# House_LED_board.net
KiCad netlist of a schematic drawn in EAGLE
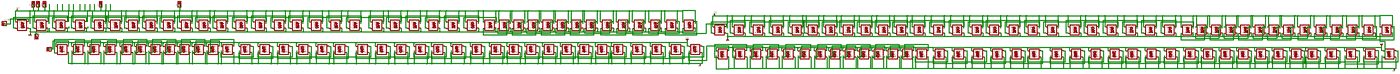
[diagram p0: schematic, sheet 1, overview]
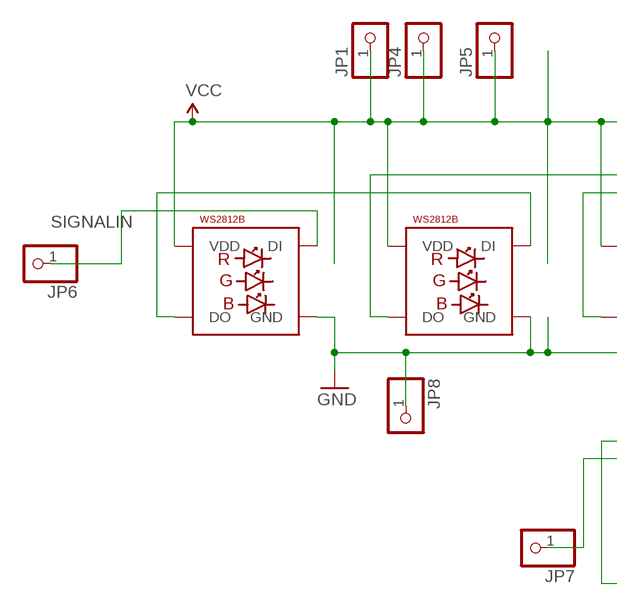
[diagram p1: schematic, sheet 1, part 1 of 8]
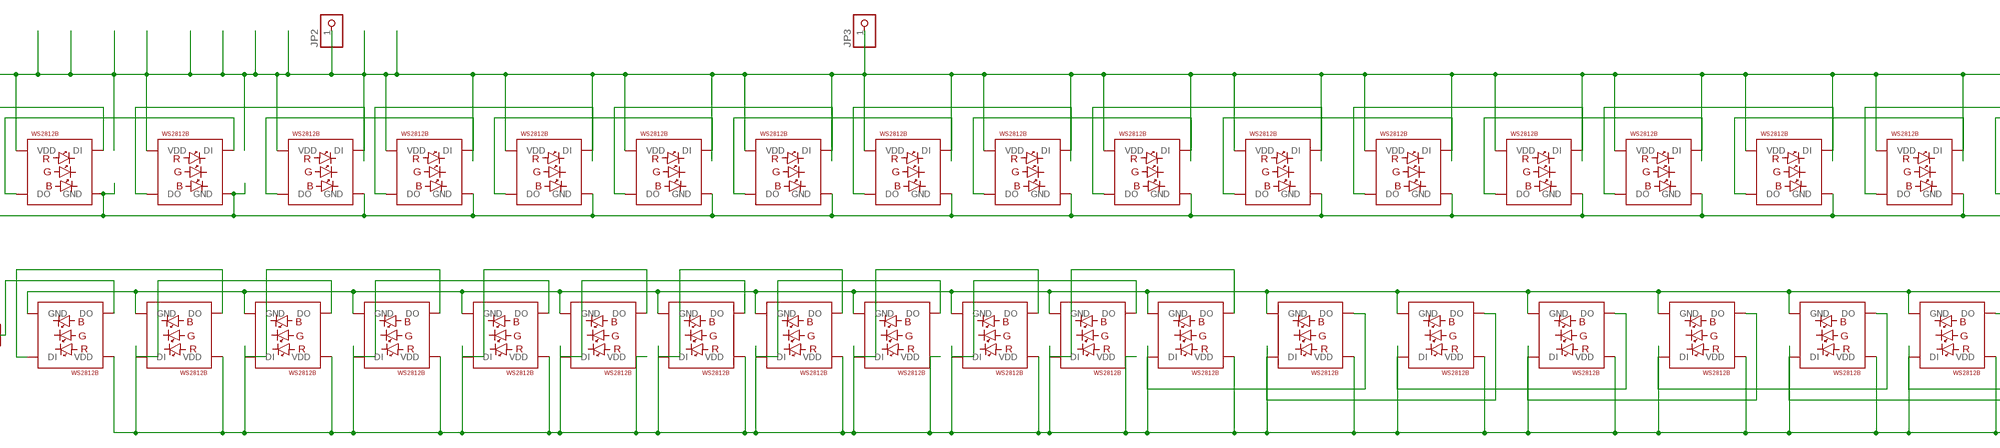
[diagram p2: schematic, sheet 1, part 2 of 8]
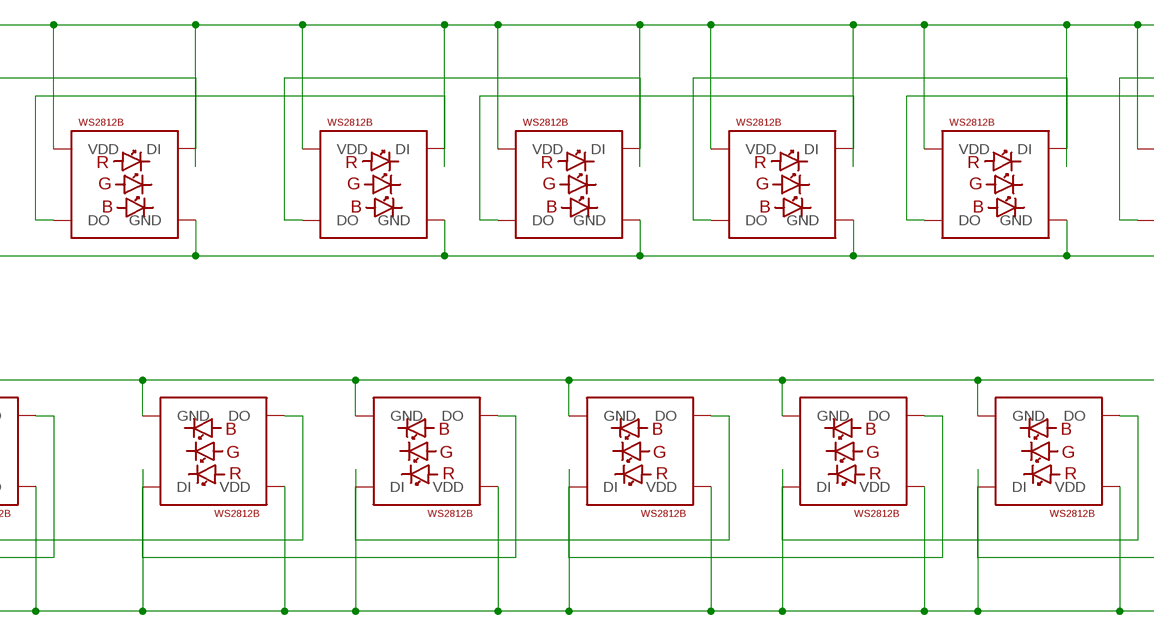
[diagram p3: schematic, sheet 1, part 3 of 8]
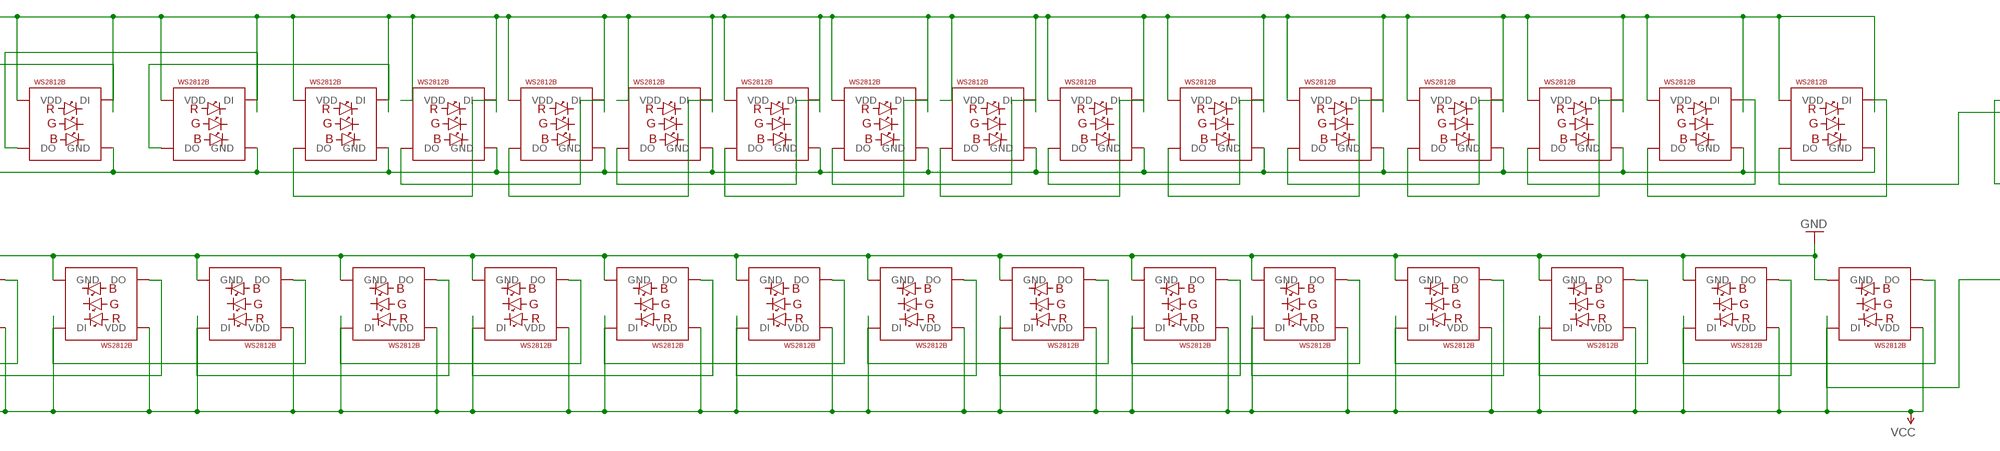
[diagram p4: schematic, sheet 1, part 4 of 8]
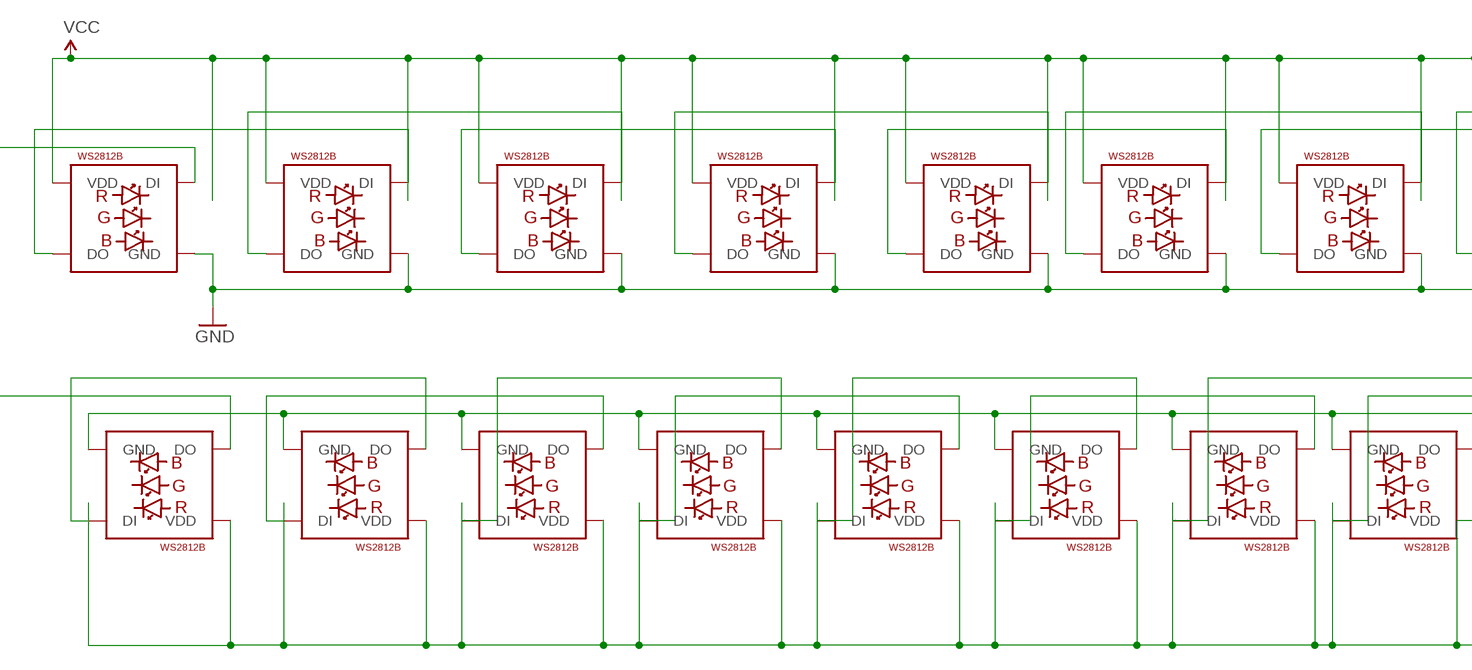
[diagram p5: schematic, sheet 1, part 5 of 8]
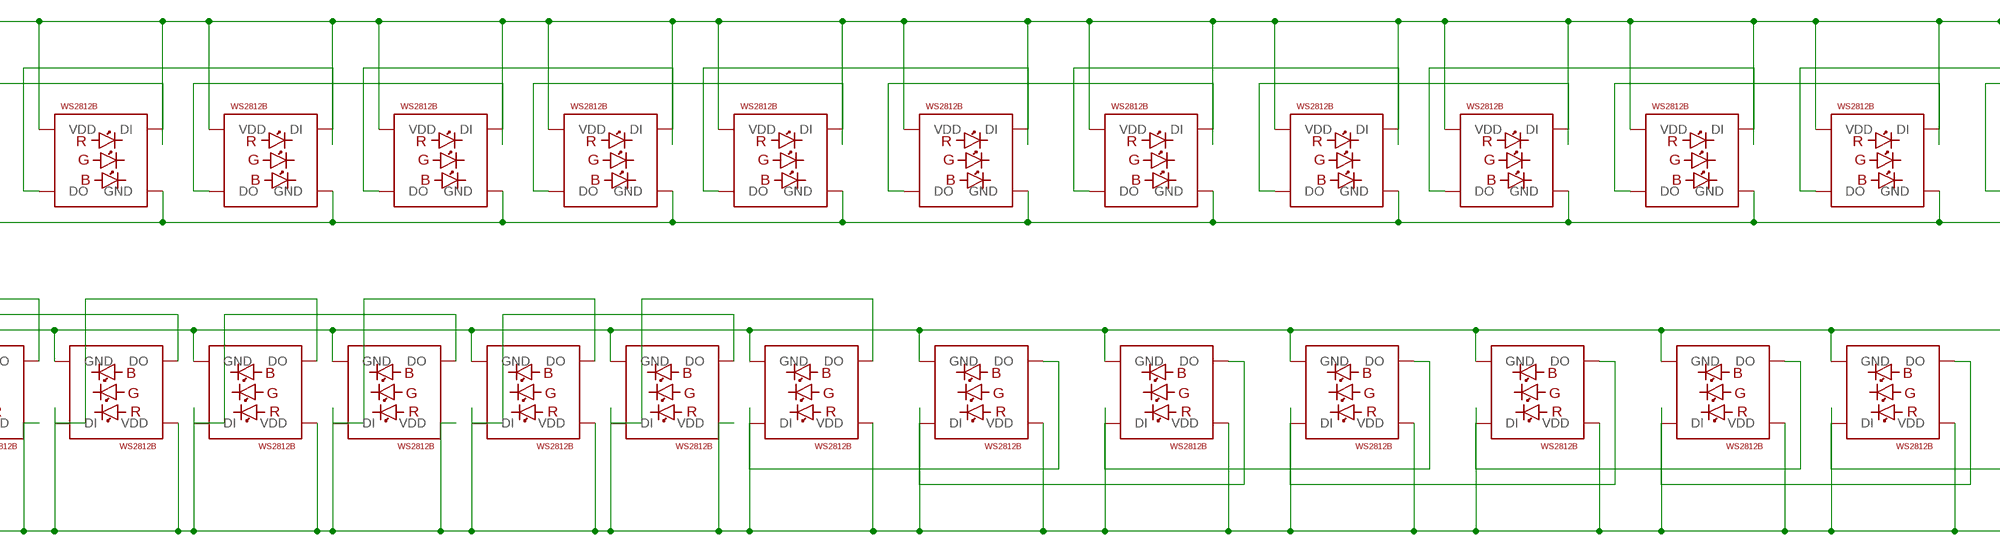
[diagram p6: schematic, sheet 1, part 6 of 8]
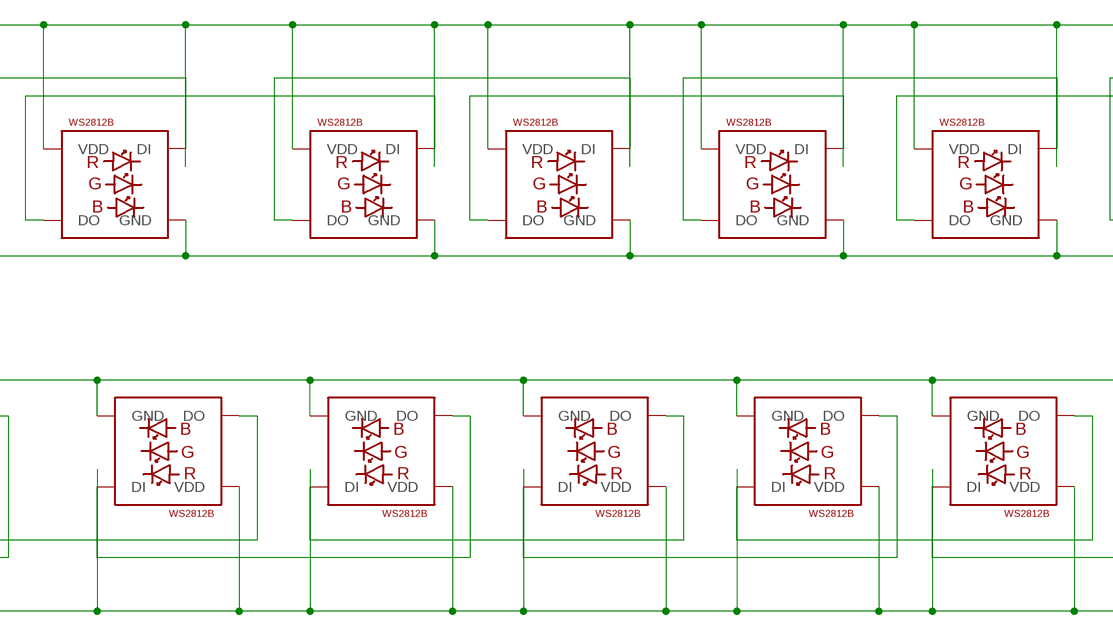
[diagram p7: schematic, sheet 1, part 7 of 8]
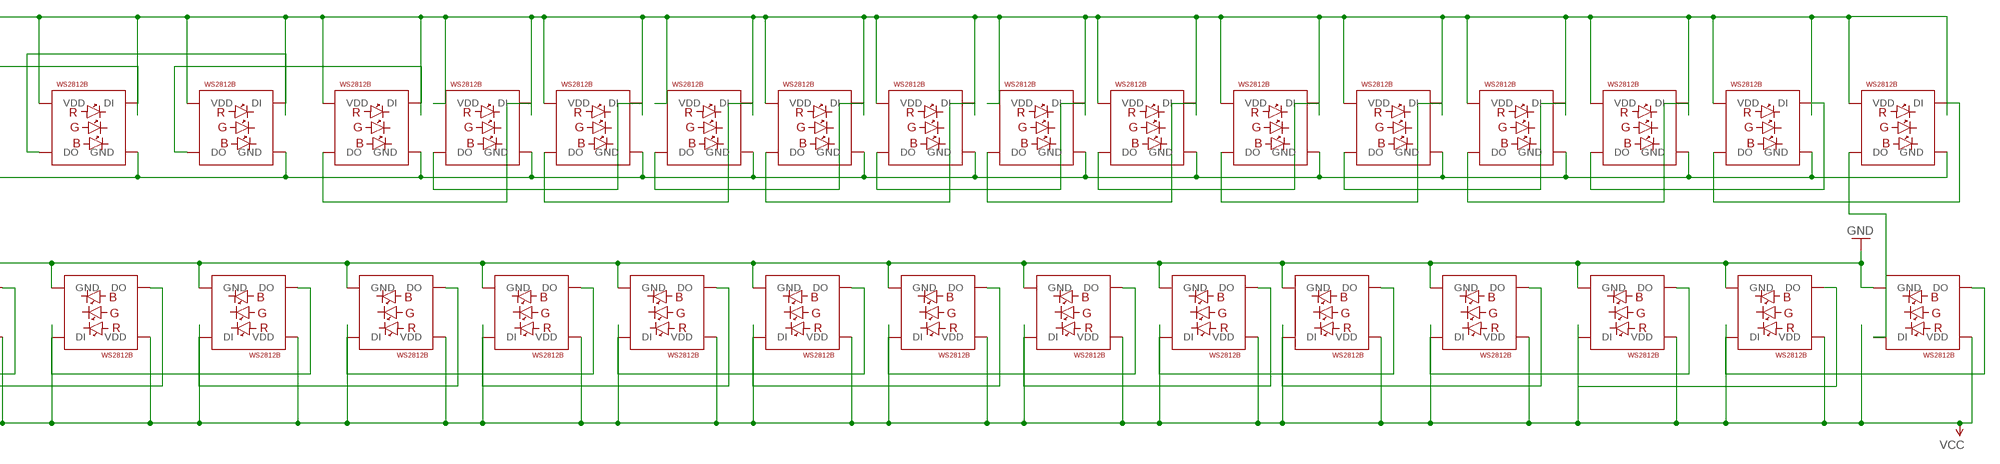
[diagram p8: schematic, sheet 1, part 8 of 8]

(export (version "E")
  (design (tool "Eeschema 10.0.6"))
  (components
    (comp (ref "JP1")
      (value "PINHD-1X1")
      (footprint "eagle-import:1X01")
      (libsource (lib "eagle-import") (part "PINHD-1X1"))
    )
    (comp (ref "JP2")
      (value "PINHD-1X1")
      (footprint "eagle-import:1X01")
      (libsource (lib "eagle-import") (part "PINHD-1X1"))
    )
    (comp (ref "JP3")
      (value "PINHD-1X1")
      (footprint "eagle-import:1X01")
      (libsource (lib "eagle-import") (part "PINHD-1X1"))
    )
    (comp (ref "JP4")
      (value "PINHD-1X1")
      (footprint "eagle-import:1X01")
      (libsource (lib "eagle-import") (part "PINHD-1X1"))
    )
    (comp (ref "JP5")
      (value "PINHD-1X1")
      (footprint "eagle-import:1X01")
      (libsource (lib "eagle-import") (part "PINHD-1X1"))
    )
    (comp (ref "JP6")
      (value "PINHD-1X1")
      (footprint "eagle-import:1X01")
      (libsource (lib "eagle-import") (part "PINHD-1X1"))
    )
    (comp (ref "JP7")
      (value "PINHD-1X1")
      (footprint "eagle-import:1X01")
      (libsource (lib "eagle-import") (part "PINHD-1X1"))
    )
    (comp (ref "JP8")
      (value "PINHD-1X1")
      (footprint "eagle-import:1X01")
      (libsource (lib "eagle-import") (part "PINHD-1X1"))
    )
    (comp (ref "LED1")
      (value "WS2812B5050")
      (footprint "eagle-import:WS2812B")
      (libsource (lib "eagle-import") (part "WS2812B5050"))
    )
    (comp (ref "LED2")
      (value "WS2812B5050")
      (footprint "eagle-import:WS2812B")
      (libsource (lib "eagle-import") (part "WS2812B5050"))
    )
    (comp (ref "LED3")
      (value "WS2812B5050")
      (footprint "eagle-import:WS2812B")
      (libsource (lib "eagle-import") (part "WS2812B5050"))
    )
    (comp (ref "LED4")
      (value "WS2812B5050")
      (footprint "eagle-import:WS2812B")
      (libsource (lib "eagle-import") (part "WS2812B5050"))
    )
    (comp (ref "LED5")
      (value "WS2812B5050")
      (footprint "eagle-import:WS2812B")
      (libsource (lib "eagle-import") (part "WS2812B5050"))
    )
    (comp (ref "LED6")
      (value "WS2812B5050")
      (footprint "eagle-import:WS2812B")
      (libsource (lib "eagle-import") (part "WS2812B5050"))
    )
    (comp (ref "LED7")
      (value "WS2812B5050")
      (footprint "eagle-import:WS2812B")
      (libsource (lib "eagle-import") (part "WS2812B5050"))
    )
    (comp (ref "LED8")
      (value "WS2812B5050")
      (footprint "eagle-import:WS2812B")
      (libsource (lib "eagle-import") (part "WS2812B5050"))
    )
    (comp (ref "LED9")
      (value "WS2812B5050")
      (footprint "eagle-import:WS2812B")
      (libsource (lib "eagle-import") (part "WS2812B5050"))
    )
    (comp (ref "LED10")
      (value "WS2812B5050")
      (footprint "eagle-import:WS2812B")
      (libsource (lib "eagle-import") (part "WS2812B5050"))
    )
    (comp (ref "LED11")
      (value "WS2812B5050")
      (footprint "eagle-import:WS2812B")
      (libsource (lib "eagle-import") (part "WS2812B5050"))
    )
    (comp (ref "LED12")
      (value "WS2812B5050")
      (footprint "eagle-import:WS2812B")
      (libsource (lib "eagle-import") (part "WS2812B5050"))
    )
    (comp (ref "LED13")
      (value "WS2812B5050")
      (footprint "eagle-import:WS2812B")
      (libsource (lib "eagle-import") (part "WS2812B5050"))
    )
    (comp (ref "LED14")
      (value "WS2812B5050")
      (footprint "eagle-import:WS2812B")
      (libsource (lib "eagle-import") (part "WS2812B5050"))
    )
    (comp (ref "LED15")
      (value "WS2812B5050")
      (footprint "eagle-import:WS2812B")
      (libsource (lib "eagle-import") (part "WS2812B5050"))
    )
    (comp (ref "LED16")
      (value "WS2812B5050")
      (footprint "eagle-import:WS2812B")
      (libsource (lib "eagle-import") (part "WS2812B5050"))
    )
    (comp (ref "LED17")
      (value "WS2812B5050")
      (footprint "eagle-import:WS2812B")
      (libsource (lib "eagle-import") (part "WS2812B5050"))
    )
    (comp (ref "LED18")
      (value "WS2812B5050")
      (footprint "eagle-import:WS2812B")
      (libsource (lib "eagle-import") (part "WS2812B5050"))
    )
    (comp (ref "LED19")
      (value "WS2812B5050")
      (footprint "eagle-import:WS2812B")
      (libsource (lib "eagle-import") (part "WS2812B5050"))
    )
    (comp (ref "LED20")
      (value "WS2812B5050")
      (footprint "eagle-import:WS2812B")
      (libsource (lib "eagle-import") (part "WS2812B5050"))
    )
    (comp (ref "LED21")
      (value "WS2812B5050")
      (footprint "eagle-import:WS2812B")
      (libsource (lib "eagle-import") (part "WS2812B5050"))
    )
    (comp (ref "LED22")
      (value "WS2812B5050")
      (footprint "eagle-import:WS2812B")
      (libsource (lib "eagle-import") (part "WS2812B5050"))
    )
    (comp (ref "LED23")
      (value "WS2812B5050")
      (footprint "eagle-import:WS2812B")
      (libsource (lib "eagle-import") (part "WS2812B5050"))
    )
    (comp (ref "LED24")
      (value "WS2812B5050")
      (footprint "eagle-import:WS2812B")
      (libsource (lib "eagle-import") (part "WS2812B5050"))
    )
    (comp (ref "LED25")
      (value "WS2812B5050")
      (footprint "eagle-import:WS2812B")
      (libsource (lib "eagle-import") (part "WS2812B5050"))
    )
    (comp (ref "LED26")
      (value "WS2812B5050")
      (footprint "eagle-import:WS2812B")
      (libsource (lib "eagle-import") (part "WS2812B5050"))
    )
    (comp (ref "LED27")
      (value "WS2812B5050")
      (footprint "eagle-import:WS2812B")
      (libsource (lib "eagle-import") (part "WS2812B5050"))
    )
    (comp (ref "LED28")
      (value "WS2812B5050")
      (footprint "eagle-import:WS2812B")
      (libsource (lib "eagle-import") (part "WS2812B5050"))
    )
    (comp (ref "LED29")
      (value "WS2812B5050")
      (footprint "eagle-import:WS2812B")
      (libsource (lib "eagle-import") (part "WS2812B5050"))
    )
    (comp (ref "LED30")
      (value "WS2812B5050")
      (footprint "eagle-import:WS2812B")
      (libsource (lib "eagle-import") (part "WS2812B5050"))
    )
    (comp (ref "LED31")
      (value "WS2812B5050")
      (footprint "eagle-import:WS2812B")
      (libsource (lib "eagle-import") (part "WS2812B5050"))
    )
    (comp (ref "LED32")
      (value "WS2812B5050")
      (footprint "eagle-import:WS2812B")
      (libsource (lib "eagle-import") (part "WS2812B5050"))
    )
    (comp (ref "LED33")
      (value "WS2812B5050")
      (footprint "eagle-import:WS2812B")
      (libsource (lib "eagle-import") (part "WS2812B5050"))
    )
    (comp (ref "LED34")
      (value "WS2812B5050")
      (footprint "eagle-import:WS2812B")
      (libsource (lib "eagle-import") (part "WS2812B5050"))
    )
    (comp (ref "LED35")
      (value "WS2812B5050")
      (footprint "eagle-import:WS2812B")
      (libsource (lib "eagle-import") (part "WS2812B5050"))
    )
    (comp (ref "LED36")
      (value "WS2812B5050")
      (footprint "eagle-import:WS2812B")
      (libsource (lib "eagle-import") (part "WS2812B5050"))
    )
    (comp (ref "LED37")
      (value "WS2812B5050")
      (footprint "eagle-import:WS2812B")
      (libsource (lib "eagle-import") (part "WS2812B5050"))
    )
    (comp (ref "LED38")
      (value "WS2812B5050")
      (footprint "eagle-import:WS2812B")
      (libsource (lib "eagle-import") (part "WS2812B5050"))
    )
    (comp (ref "LED39")
      (value "WS2812B5050")
      (footprint "eagle-import:WS2812B")
      (libsource (lib "eagle-import") (part "WS2812B5050"))
    )
    (comp (ref "LED40")
      (value "WS2812B5050")
      (footprint "eagle-import:WS2812B")
      (libsource (lib "eagle-import") (part "WS2812B5050"))
    )
    (comp (ref "LED41")
      (value "WS2812B5050")
      (footprint "eagle-import:WS2812B")
      (libsource (lib "eagle-import") (part "WS2812B5050"))
    )
    (comp (ref "LED42")
      (value "WS2812B5050")
      (footprint "eagle-import:WS2812B")
      (libsource (lib "eagle-import") (part "WS2812B5050"))
    )
    (comp (ref "LED43")
      (value "WS2812B5050")
      (footprint "eagle-import:WS2812B")
      (libsource (lib "eagle-import") (part "WS2812B5050"))
    )
    (comp (ref "LED44")
      (value "WS2812B5050")
      (footprint "eagle-import:WS2812B")
      (libsource (lib "eagle-import") (part "WS2812B5050"))
    )
    (comp (ref "LED45")
      (value "WS2812B5050")
      (footprint "eagle-import:WS2812B")
      (libsource (lib "eagle-import") (part "WS2812B5050"))
    )
    (comp (ref "LED46")
      (value "WS2812B5050")
      (footprint "eagle-import:WS2812B")
      (libsource (lib "eagle-import") (part "WS2812B5050"))
    )
    (comp (ref "LED47")
      (value "WS2812B5050")
      (footprint "eagle-import:WS2812B")
      (libsource (lib "eagle-import") (part "WS2812B5050"))
    )
    (comp (ref "LED48")
      (value "WS2812B5050")
      (footprint "eagle-import:WS2812B")
      (libsource (lib "eagle-import") (part "WS2812B5050"))
    )
    (comp (ref "LED49")
      (value "WS2812B5050")
      (footprint "eagle-import:WS2812B")
      (libsource (lib "eagle-import") (part "WS2812B5050"))
    )
    (comp (ref "LED50")
      (value "WS2812B5050")
      (footprint "eagle-import:WS2812B")
      (libsource (lib "eagle-import") (part "WS2812B5050"))
    )
    (comp (ref "LED51")
      (value "WS2812B5050")
      (footprint "eagle-import:WS2812B")
      (libsource (lib "eagle-import") (part "WS2812B5050"))
    )
    (comp (ref "LED52")
      (value "WS2812B5050")
      (footprint "eagle-import:WS2812B")
      (libsource (lib "eagle-import") (part "WS2812B5050"))
    )
    (comp (ref "LED53")
      (value "WS2812B5050")
      (footprint "eagle-import:WS2812B")
      (libsource (lib "eagle-import") (part "WS2812B5050"))
    )
    (comp (ref "LED54")
      (value "WS2812B5050")
      (footprint "eagle-import:WS2812B")
      (libsource (lib "eagle-import") (part "WS2812B5050"))
    )
    (comp (ref "LED55")
      (value "WS2812B5050")
      (footprint "eagle-import:WS2812B")
      (libsource (lib "eagle-import") (part "WS2812B5050"))
    )
    (comp (ref "LED56")
      (value "WS2812B5050")
      (footprint "eagle-import:WS2812B")
      (libsource (lib "eagle-import") (part "WS2812B5050"))
    )
    (comp (ref "LED57")
      (value "WS2812B5050")
      (footprint "eagle-import:WS2812B")
      (libsource (lib "eagle-import") (part "WS2812B5050"))
    )
    (comp (ref "LED58")
      (value "WS2812B5050")
      (footprint "eagle-import:WS2812B")
      (libsource (lib "eagle-import") (part "WS2812B5050"))
    )
    (comp (ref "LED59")
      (value "WS2812B5050")
      (footprint "eagle-import:WS2812B")
      (libsource (lib "eagle-import") (part "WS2812B5050"))
    )
    (comp (ref "LED60")
      (value "WS2812B5050")
      (footprint "eagle-import:WS2812B")
      (libsource (lib "eagle-import") (part "WS2812B5050"))
    )
    (comp (ref "LED61")
      (value "WS2812B5050")
      (footprint "eagle-import:WS2812B")
      (libsource (lib "eagle-import") (part "WS2812B5050"))
    )
    (comp (ref "LED62")
      (value "WS2812B5050")
      (footprint "eagle-import:WS2812B")
      (libsource (lib "eagle-import") (part "WS2812B5050"))
    )
    (comp (ref "LED63")
      (value "WS2812B5050")
      (footprint "eagle-import:WS2812B")
      (libsource (lib "eagle-import") (part "WS2812B5050"))
    )
    (comp (ref "LED64")
      (value "WS2812B5050")
      (footprint "eagle-import:WS2812B")
      (libsource (lib "eagle-import") (part "WS2812B5050"))
    )
    (comp (ref "LED65")
      (value "WS2812B5050")
      (footprint "eagle-import:WS2812B")
      (libsource (lib "eagle-import") (part "WS2812B5050"))
    )
    (comp (ref "LED66")
      (value "WS2812B5050")
      (footprint "eagle-import:WS2812B")
      (libsource (lib "eagle-import") (part "WS2812B5050"))
    )
    (comp (ref "LED67")
      (value "WS2812B5050")
      (footprint "eagle-import:WS2812B")
      (libsource (lib "eagle-import") (part "WS2812B5050"))
    )
    (comp (ref "LED68")
      (value "WS2812B5050")
      (footprint "eagle-import:WS2812B")
      (libsource (lib "eagle-import") (part "WS2812B5050"))
    )
    (comp (ref "LED69")
      (value "WS2812B5050")
      (footprint "eagle-import:WS2812B")
      (libsource (lib "eagle-import") (part "WS2812B5050"))
    )
    (comp (ref "LED70")
      (value "WS2812B5050")
      (footprint "eagle-import:WS2812B")
      (libsource (lib "eagle-import") (part "WS2812B5050"))
    )
    (comp (ref "LED71")
      (value "WS2812B5050")
      (footprint "eagle-import:WS2812B")
      (libsource (lib "eagle-import") (part "WS2812B5050"))
    )
    (comp (ref "LED72")
      (value "WS2812B5050")
      (footprint "eagle-import:WS2812B")
      (libsource (lib "eagle-import") (part "WS2812B5050"))
    )
    (comp (ref "LED73")
      (value "WS2812B5050")
      (footprint "eagle-import:WS2812B")
      (libsource (lib "eagle-import") (part "WS2812B5050"))
    )
    (comp (ref "LED74")
      (value "WS2812B5050")
      (footprint "eagle-import:WS2812B")
      (libsource (lib "eagle-import") (part "WS2812B5050"))
    )
    (comp (ref "LED75")
      (value "WS2812B5050")
      (footprint "eagle-import:WS2812B")
      (libsource (lib "eagle-import") (part "WS2812B5050"))
    )
    (comp (ref "LED76")
      (value "WS2812B5050")
      (footprint "eagle-import:WS2812B")
      (libsource (lib "eagle-import") (part "WS2812B5050"))
    )
    (comp (ref "LED77")
      (value "WS2812B5050")
      (footprint "eagle-import:WS2812B")
      (libsource (lib "eagle-import") (part "WS2812B5050"))
    )
    (comp (ref "LED78")
      (value "WS2812B5050")
      (footprint "eagle-import:WS2812B")
      (libsource (lib "eagle-import") (part "WS2812B5050"))
    )
    (comp (ref "LED79")
      (value "WS2812B5050")
      (footprint "eagle-import:WS2812B")
      (libsource (lib "eagle-import") (part "WS2812B5050"))
    )
    (comp (ref "LED80")
      (value "WS2812B5050")
      (footprint "eagle-import:WS2812B")
      (libsource (lib "eagle-import") (part "WS2812B5050"))
    )
    (comp (ref "LED81")
      (value "WS2812B5050")
      (footprint "eagle-import:WS2812B")
      (libsource (lib "eagle-import") (part "WS2812B5050"))
    )
    (comp (ref "LED82")
      (value "WS2812B5050")
      (footprint "eagle-import:WS2812B")
      (libsource (lib "eagle-import") (part "WS2812B5050"))
    )
    (comp (ref "LED83")
      (value "WS2812B5050")
      (footprint "eagle-import:WS2812B")
      (libsource (lib "eagle-import") (part "WS2812B5050"))
    )
    (comp (ref "LED84")
      (value "WS2812B5050")
      (footprint "eagle-import:WS2812B")
      (libsource (lib "eagle-import") (part "WS2812B5050"))
    )
    (comp (ref "LED85")
      (value "WS2812B5050")
      (footprint "eagle-import:WS2812B")
      (libsource (lib "eagle-import") (part "WS2812B5050"))
    )
    (comp (ref "LED86")
      (value "WS2812B5050")
      (footprint "eagle-import:WS2812B")
      (libsource (lib "eagle-import") (part "WS2812B5050"))
    )
    (comp (ref "LED87")
      (value "WS2812B5050")
      (footprint "eagle-import:WS2812B")
      (libsource (lib "eagle-import") (part "WS2812B5050"))
    )
    (comp (ref "LED88")
      (value "WS2812B5050")
      (footprint "eagle-import:WS2812B")
      (libsource (lib "eagle-import") (part "WS2812B5050"))
    )
    (comp (ref "LED89")
      (value "WS2812B5050")
      (footprint "eagle-import:WS2812B")
      (libsource (lib "eagle-import") (part "WS2812B5050"))
    )
    (comp (ref "LED90")
      (value "WS2812B5050")
      (footprint "eagle-import:WS2812B")
      (libsource (lib "eagle-import") (part "WS2812B5050"))
    )
    (comp (ref "LED91")
      (value "WS2812B5050")
      (footprint "eagle-import:WS2812B")
      (libsource (lib "eagle-import") (part "WS2812B5050"))
    )
    (comp (ref "LED92")
      (value "WS2812B5050")
      (footprint "eagle-import:WS2812B")
      (libsource (lib "eagle-import") (part "WS2812B5050"))
    )
    (comp (ref "LED93")
      (value "WS2812B5050")
      (footprint "eagle-import:WS2812B")
      (libsource (lib "eagle-import") (part "WS2812B5050"))
    )
    (comp (ref "LED94")
      (value "WS2812B5050")
      (footprint "eagle-import:WS2812B")
      (libsource (lib "eagle-import") (part "WS2812B5050"))
    )
    (comp (ref "LED95")
      (value "WS2812B5050")
      (footprint "eagle-import:WS2812B")
      (libsource (lib "eagle-import") (part "WS2812B5050"))
    )
    (comp (ref "LED96")
      (value "WS2812B5050")
      (footprint "eagle-import:WS2812B")
      (libsource (lib "eagle-import") (part "WS2812B5050"))
    )
    (comp (ref "LED97")
      (value "WS2812B5050")
      (footprint "eagle-import:WS2812B")
      (libsource (lib "eagle-import") (part "WS2812B5050"))
    )
    (comp (ref "LED98")
      (value "WS2812B5050")
      (footprint "eagle-import:WS2812B")
      (libsource (lib "eagle-import") (part "WS2812B5050"))
    )
    (comp (ref "LED99")
      (value "WS2812B5050")
      (footprint "eagle-import:WS2812B")
      (libsource (lib "eagle-import") (part "WS2812B5050"))
    )
    (comp (ref "LED100")
      (value "WS2812B5050")
      (footprint "eagle-import:WS2812B")
      (libsource (lib "eagle-import") (part "WS2812B5050"))
    )
    (comp (ref "LED101")
      (value "WS2812B5050")
      (footprint "eagle-import:WS2812B")
      (libsource (lib "eagle-import") (part "WS2812B5050"))
    )
    (comp (ref "LED102")
      (value "WS2812B5050")
      (footprint "eagle-import:WS2812B")
      (libsource (lib "eagle-import") (part "WS2812B5050"))
    )
    (comp (ref "LED103")
      (value "WS2812B5050")
      (footprint "eagle-import:WS2812B")
      (libsource (lib "eagle-import") (part "WS2812B5050"))
    )
    (comp (ref "LED104")
      (value "WS2812B5050")
      (footprint "eagle-import:WS2812B")
      (libsource (lib "eagle-import") (part "WS2812B5050"))
    )
    (comp (ref "LED105")
      (value "WS2812B5050")
      (footprint "eagle-import:WS2812B")
      (libsource (lib "eagle-import") (part "WS2812B5050"))
    )
    (comp (ref "LED106")
      (value "WS2812B5050")
      (footprint "eagle-import:WS2812B")
      (libsource (lib "eagle-import") (part "WS2812B5050"))
    )
    (comp (ref "LED107")
      (value "WS2812B5050")
      (footprint "eagle-import:WS2812B")
      (libsource (lib "eagle-import") (part "WS2812B5050"))
    )
    (comp (ref "LED108")
      (value "WS2812B5050")
      (footprint "eagle-import:WS2812B")
      (libsource (lib "eagle-import") (part "WS2812B5050"))
    )
    (comp (ref "LED109")
      (value "WS2812B5050")
      (footprint "eagle-import:WS2812B")
      (libsource (lib "eagle-import") (part "WS2812B5050"))
    )
    (comp (ref "LED110")
      (value "WS2812B5050")
      (footprint "eagle-import:WS2812B")
      (libsource (lib "eagle-import") (part "WS2812B5050"))
    )
    (comp (ref "LED111")
      (value "WS2812B5050")
      (footprint "eagle-import:WS2812B")
      (libsource (lib "eagle-import") (part "WS2812B5050"))
    )
    (comp (ref "LED112")
      (value "WS2812B5050")
      (footprint "eagle-import:WS2812B")
      (libsource (lib "eagle-import") (part "WS2812B5050"))
    )
    (comp (ref "LED113")
      (value "WS2812B5050")
      (footprint "eagle-import:WS2812B")
      (libsource (lib "eagle-import") (part "WS2812B5050"))
    )
    (comp (ref "LED114")
      (value "WS2812B5050")
      (footprint "eagle-import:WS2812B")
      (libsource (lib "eagle-import") (part "WS2812B5050"))
    )
    (comp (ref "LED115")
      (value "WS2812B5050")
      (footprint "eagle-import:WS2812B")
      (libsource (lib "eagle-import") (part "WS2812B5050"))
    )
    (comp (ref "LED116")
      (value "WS2812B5050")
      (footprint "eagle-import:WS2812B")
      (libsource (lib "eagle-import") (part "WS2812B5050"))
    )
    (comp (ref "LED117")
      (value "WS2812B5050")
      (footprint "eagle-import:WS2812B")
      (libsource (lib "eagle-import") (part "WS2812B5050"))
    )
    (comp (ref "LED118")
      (value "WS2812B5050")
      (footprint "eagle-import:WS2812B")
      (libsource (lib "eagle-import") (part "WS2812B5050"))
    )
    (comp (ref "LED119")
      (value "WS2812B5050")
      (footprint "eagle-import:WS2812B")
      (libsource (lib "eagle-import") (part "WS2812B5050"))
    )
    (comp (ref "LED120")
      (value "WS2812B5050")
      (footprint "eagle-import:WS2812B")
      (libsource (lib "eagle-import") (part "WS2812B5050"))
    )
    (comp (ref "LED121")
      (value "WS2812B5050")
      (footprint "eagle-import:WS2812B")
      (libsource (lib "eagle-import") (part "WS2812B5050"))
    )
    (comp (ref "LED122")
      (value "WS2812B5050")
      (footprint "eagle-import:WS2812B")
      (libsource (lib "eagle-import") (part "WS2812B5050"))
    )
    (comp (ref "LED123")
      (value "WS2812B5050")
      (footprint "eagle-import:WS2812B")
      (libsource (lib "eagle-import") (part "WS2812B5050"))
    )
    (comp (ref "LED124")
      (value "WS2812B5050")
      (footprint "eagle-import:WS2812B")
      (libsource (lib "eagle-import") (part "WS2812B5050"))
    )
    (comp (ref "LED125")
      (value "WS2812B5050")
      (footprint "eagle-import:WS2812B")
      (libsource (lib "eagle-import") (part "WS2812B5050"))
    )
    (comp (ref "LED126")
      (value "WS2812B5050")
      (footprint "eagle-import:WS2812B")
      (libsource (lib "eagle-import") (part "WS2812B5050"))
    )
    (comp (ref "LED127")
      (value "WS2812B5050")
      (footprint "eagle-import:WS2812B")
      (libsource (lib "eagle-import") (part "WS2812B5050"))
    )
    (comp (ref "LED128")
      (value "WS2812B5050")
      (footprint "eagle-import:WS2812B")
      (libsource (lib "eagle-import") (part "WS2812B5050"))
    )
    (comp (ref "LED129")
      (value "WS2812B5050")
      (footprint "eagle-import:WS2812B")
      (libsource (lib "eagle-import") (part "WS2812B5050"))
    )
    (comp (ref "LED130")
      (value "WS2812B5050")
      (footprint "eagle-import:WS2812B")
      (libsource (lib "eagle-import") (part "WS2812B5050"))
    )
    (comp (ref "LED131")
      (value "WS2812B5050")
      (footprint "eagle-import:WS2812B")
      (libsource (lib "eagle-import") (part "WS2812B5050"))
    )
    (comp (ref "LED132")
      (value "WS2812B5050")
      (footprint "eagle-import:WS2812B")
      (libsource (lib "eagle-import") (part "WS2812B5050"))
    )
    (comp (ref "LED133")
      (value "WS2812B5050")
      (footprint "eagle-import:WS2812B")
      (libsource (lib "eagle-import") (part "WS2812B5050"))
    )
    (comp (ref "LED134")
      (value "WS2812B5050")
      (footprint "eagle-import:WS2812B")
      (libsource (lib "eagle-import") (part "WS2812B5050"))
    )
    (comp (ref "LED135")
      (value "WS2812B5050")
      (footprint "eagle-import:WS2812B")
      (libsource (lib "eagle-import") (part "WS2812B5050"))
    )
    (comp (ref "LED136")
      (value "WS2812B5050")
      (footprint "eagle-import:WS2812B")
      (libsource (lib "eagle-import") (part "WS2812B5050"))
    )
    (comp (ref "LED137")
      (value "WS2812B5050")
      (footprint "eagle-import:WS2812B")
      (libsource (lib "eagle-import") (part "WS2812B5050"))
    )
    (comp (ref "LED138")
      (value "WS2812B5050")
      (footprint "eagle-import:WS2812B")
      (libsource (lib "eagle-import") (part "WS2812B5050"))
    )
    (comp (ref "LED139")
      (value "WS2812B5050")
      (footprint "eagle-import:WS2812B")
      (libsource (lib "eagle-import") (part "WS2812B5050"))
    )
    (comp (ref "LED140")
      (value "WS2812B5050")
      (footprint "eagle-import:WS2812B")
      (libsource (lib "eagle-import") (part "WS2812B5050"))
    )
    (comp (ref "LED141")
      (value "WS2812B5050")
      (footprint "eagle-import:WS2812B")
      (libsource (lib "eagle-import") (part "WS2812B5050"))
    )
    (comp (ref "LED142")
      (value "WS2812B5050")
      (footprint "eagle-import:WS2812B")
      (libsource (lib "eagle-import") (part "WS2812B5050"))
    )
    (comp (ref "LED143")
      (value "WS2812B5050")
      (footprint "eagle-import:WS2812B")
      (libsource (lib "eagle-import") (part "WS2812B5050"))
    )
    (comp (ref "LED144")
      (value "WS2812B5050")
      (footprint "eagle-import:WS2812B")
      (libsource (lib "eagle-import") (part "WS2812B5050"))
    )
    (comp (ref "LED145")
      (value "WS2812B5050")
      (footprint "eagle-import:WS2812B")
      (libsource (lib "eagle-import") (part "WS2812B5050"))
    )
    (comp (ref "LED146")
      (value "WS2812B5050")
      (footprint "eagle-import:WS2812B")
      (libsource (lib "eagle-import") (part "WS2812B5050"))
    )
    (comp (ref "LED147")
      (value "WS2812B5050")
      (footprint "eagle-import:WS2812B")
      (libsource (lib "eagle-import") (part "WS2812B5050"))
    )
    (comp (ref "LED148")
      (value "WS2812B5050")
      (footprint "eagle-import:WS2812B")
      (libsource (lib "eagle-import") (part "WS2812B5050"))
    )
    (comp (ref "LED149")
      (value "WS2812B5050")
      (footprint "eagle-import:WS2812B")
      (libsource (lib "eagle-import") (part "WS2812B5050"))
    )
    (comp (ref "LED150")
      (value "WS2812B5050")
      (footprint "eagle-import:WS2812B")
      (libsource (lib "eagle-import") (part "WS2812B5050"))
    )
    (comp (ref "LED151")
      (value "WS2812B5050")
      (footprint "eagle-import:WS2812B")
      (libsource (lib "eagle-import") (part "WS2812B5050"))
    )
    (comp (ref "LED152")
      (value "WS2812B5050")
      (footprint "eagle-import:WS2812B")
      (libsource (lib "eagle-import") (part "WS2812B5050"))
    )
    (comp (ref "LED153")
      (value "WS2812B5050")
      (footprint "eagle-import:WS2812B")
      (libsource (lib "eagle-import") (part "WS2812B5050"))
    )
    (comp (ref "LED154")
      (value "WS2812B5050")
      (footprint "eagle-import:WS2812B")
      (libsource (lib "eagle-import") (part "WS2812B5050"))
    )
  )
  (nets
    (net (code "1") (name "/SIGNALIN") (class "Default")
      (node (ref "JP6") (pin "1") (pinfunction "1_1") (pintype "passive"))
      (node (ref "LED1") (pin "4-DIN") (pinfunction "DI_4-DIN") (pintype "input"))
    )
    (net (code "2") (name "GND") (class "Default")
      (node (ref "JP8") (pin "1") (pinfunction "1_1") (pintype "passive"))
      (node (ref "LED1") (pin "3-GND") (pinfunction "GND_3-GND") (pintype "power_in"))
      (node (ref "LED10") (pin "3-GND") (pinfunction "GND_3-GND") (pintype "power_in"))
      (node (ref "LED100") (pin "3-GND") (pinfunction "GND_3-GND") (pintype "power_in"))
      (node (ref "LED101") (pin "3-GND") (pinfunction "GND_3-GND") (pintype "power_in"))
      (node (ref "LED102") (pin "3-GND") (pinfunction "GND_3-GND") (pintype "power_in"))
      (node (ref "LED103") (pin "3-GND") (pinfunction "GND_3-GND") (pintype "power_in"))
      (node (ref "LED104") (pin "3-GND") (pinfunction "GND_3-GND") (pintype "power_in"))
      (node (ref "LED105") (pin "3-GND") (pinfunction "GND_3-GND") (pintype "power_in"))
      (node (ref "LED106") (pin "3-GND") (pinfunction "GND_3-GND") (pintype "power_in"))
      (node (ref "LED107") (pin "3-GND") (pinfunction "GND_3-GND") (pintype "power_in"))
      (node (ref "LED108") (pin "3-GND") (pinfunction "GND_3-GND") (pintype "power_in"))
      (node (ref "LED109") (pin "3-GND") (pinfunction "GND_3-GND") (pintype "power_in"))
      (node (ref "LED11") (pin "3-GND") (pinfunction "GND_3-GND") (pintype "power_in"))
      (node (ref "LED110") (pin "3-GND") (pinfunction "GND_3-GND") (pintype "power_in"))
      (node (ref "LED111") (pin "3-GND") (pinfunction "GND_3-GND") (pintype "power_in"))
      (node (ref "LED112") (pin "3-GND") (pinfunction "GND_3-GND") (pintype "power_in"))
      (node (ref "LED113") (pin "3-GND") (pinfunction "GND_3-GND") (pintype "power_in"))
      (node (ref "LED114") (pin "3-GND") (pinfunction "GND_3-GND") (pintype "power_in"))
      (node (ref "LED115") (pin "3-GND") (pinfunction "GND_3-GND") (pintype "power_in"))
      (node (ref "LED116") (pin "3-GND") (pinfunction "GND_3-GND") (pintype "power_in"))
      (node (ref "LED117") (pin "3-GND") (pinfunction "GND_3-GND") (pintype "power_in"))
      (node (ref "LED118") (pin "3-GND") (pinfunction "GND_3-GND") (pintype "power_in"))
      (node (ref "LED119") (pin "3-GND") (pinfunction "GND_3-GND") (pintype "power_in"))
      (node (ref "LED12") (pin "3-GND") (pinfunction "GND_3-GND") (pintype "power_in"))
      (node (ref "LED120") (pin "3-GND") (pinfunction "GND_3-GND") (pintype "power_in"))
      (node (ref "LED121") (pin "3-GND") (pinfunction "GND_3-GND") (pintype "power_in"))
      (node (ref "LED122") (pin "3-GND") (pinfunction "GND_3-GND") (pintype "power_in"))
      (node (ref "LED123") (pin "3-GND") (pinfunction "GND_3-GND") (pintype "power_in"))
      (node (ref "LED124") (pin "3-GND") (pinfunction "GND_3-GND") (pintype "power_in"))
      (node (ref "LED125") (pin "3-GND") (pinfunction "GND_3-GND") (pintype "power_in"))
      (node (ref "LED126") (pin "3-GND") (pinfunction "GND_3-GND") (pintype "power_in"))
      (node (ref "LED127") (pin "3-GND") (pinfunction "GND_3-GND") (pintype "power_in"))
      (node (ref "LED128") (pin "3-GND") (pinfunction "GND_3-GND") (pintype "power_in"))
      (node (ref "LED129") (pin "3-GND") (pinfunction "GND_3-GND") (pintype "power_in"))
      (node (ref "LED13") (pin "3-GND") (pinfunction "GND_3-GND") (pintype "power_in"))
      (node (ref "LED130") (pin "3-GND") (pinfunction "GND_3-GND") (pintype "power_in"))
      (node (ref "LED131") (pin "3-GND") (pinfunction "GND_3-GND") (pintype "power_in"))
      (node (ref "LED132") (pin "3-GND") (pinfunction "GND_3-GND") (pintype "power_in"))
      (node (ref "LED133") (pin "3-GND") (pinfunction "GND_3-GND") (pintype "power_in"))
      (node (ref "LED134") (pin "3-GND") (pinfunction "GND_3-GND") (pintype "power_in"))
      (node (ref "LED135") (pin "3-GND") (pinfunction "GND_3-GND") (pintype "power_in"))
      (node (ref "LED136") (pin "3-GND") (pinfunction "GND_3-GND") (pintype "power_in"))
      (node (ref "LED137") (pin "3-GND") (pinfunction "GND_3-GND") (pintype "power_in"))
      (node (ref "LED138") (pin "3-GND") (pinfunction "GND_3-GND") (pintype "power_in"))
      (node (ref "LED139") (pin "3-GND") (pinfunction "GND_3-GND") (pintype "power_in"))
      (node (ref "LED14") (pin "3-GND") (pinfunction "GND_3-GND") (pintype "power_in"))
      (node (ref "LED140") (pin "3-GND") (pinfunction "GND_3-GND") (pintype "power_in"))
      (node (ref "LED141") (pin "3-GND") (pinfunction "GND_3-GND") (pintype "power_in"))
      (node (ref "LED142") (pin "3-GND") (pinfunction "GND_3-GND") (pintype "power_in"))
      (node (ref "LED143") (pin "3-GND") (pinfunction "GND_3-GND") (pintype "power_in"))
      (node (ref "LED144") (pin "3-GND") (pinfunction "GND_3-GND") (pintype "power_in"))
      (node (ref "LED145") (pin "3-GND") (pinfunction "GND_3-GND") (pintype "power_in"))
      (node (ref "LED146") (pin "3-GND") (pinfunction "GND_3-GND") (pintype "power_in"))
      (node (ref "LED147") (pin "3-GND") (pinfunction "GND_3-GND") (pintype "power_in"))
      (node (ref "LED148") (pin "3-GND") (pinfunction "GND_3-GND") (pintype "power_in"))
      (node (ref "LED149") (pin "3-GND") (pinfunction "GND_3-GND") (pintype "power_in"))
      (node (ref "LED15") (pin "3-GND") (pinfunction "GND_3-GND") (pintype "power_in"))
      (node (ref "LED150") (pin "3-GND") (pinfunction "GND_3-GND") (pintype "power_in"))
      (node (ref "LED151") (pin "3-GND") (pinfunction "GND_3-GND") (pintype "power_in"))
      (node (ref "LED152") (pin "3-GND") (pinfunction "GND_3-GND") (pintype "power_in"))
      (node (ref "LED153") (pin "3-GND") (pinfunction "GND_3-GND") (pintype "power_in"))
      (node (ref "LED154") (pin "3-GND") (pinfunction "GND_3-GND") (pintype "power_in"))
      (node (ref "LED16") (pin "3-GND") (pinfunction "GND_3-GND") (pintype "power_in"))
      (node (ref "LED17") (pin "3-GND") (pinfunction "GND_3-GND") (pintype "power_in"))
      (node (ref "LED18") (pin "3-GND") (pinfunction "GND_3-GND") (pintype "power_in"))
      (node (ref "LED19") (pin "3-GND") (pinfunction "GND_3-GND") (pintype "power_in"))
      (node (ref "LED2") (pin "3-GND") (pinfunction "GND_3-GND") (pintype "power_in"))
      (node (ref "LED20") (pin "3-GND") (pinfunction "GND_3-GND") (pintype "power_in"))
      (node (ref "LED21") (pin "3-GND") (pinfunction "GND_3-GND") (pintype "power_in"))
      (node (ref "LED22") (pin "3-GND") (pinfunction "GND_3-GND") (pintype "power_in"))
      (node (ref "LED23") (pin "3-GND") (pinfunction "GND_3-GND") (pintype "power_in"))
      (node (ref "LED24") (pin "3-GND") (pinfunction "GND_3-GND") (pintype "power_in"))
      (node (ref "LED25") (pin "3-GND") (pinfunction "GND_3-GND") (pintype "power_in"))
      (node (ref "LED26") (pin "3-GND") (pinfunction "GND_3-GND") (pintype "power_in"))
      (node (ref "LED27") (pin "3-GND") (pinfunction "GND_3-GND") (pintype "power_in"))
      (node (ref "LED28") (pin "3-GND") (pinfunction "GND_3-GND") (pintype "power_in"))
      (node (ref "LED29") (pin "3-GND") (pinfunction "GND_3-GND") (pintype "power_in"))
      (node (ref "LED3") (pin "3-GND") (pinfunction "GND_3-GND") (pintype "power_in"))
      (node (ref "LED30") (pin "3-GND") (pinfunction "GND_3-GND") (pintype "power_in"))
      (node (ref "LED31") (pin "3-GND") (pinfunction "GND_3-GND") (pintype "power_in"))
      (node (ref "LED32") (pin "3-GND") (pinfunction "GND_3-GND") (pintype "power_in"))
      (node (ref "LED33") (pin "3-GND") (pinfunction "GND_3-GND") (pintype "power_in"))
      (node (ref "LED34") (pin "3-GND") (pinfunction "GND_3-GND") (pintype "power_in"))
      (node (ref "LED35") (pin "3-GND") (pinfunction "GND_3-GND") (pintype "power_in"))
      (node (ref "LED36") (pin "3-GND") (pinfunction "GND_3-GND") (pintype "power_in"))
      (node (ref "LED37") (pin "3-GND") (pinfunction "GND_3-GND") (pintype "power_in"))
      (node (ref "LED38") (pin "3-GND") (pinfunction "GND_3-GND") (pintype "power_in"))
      (node (ref "LED39") (pin "3-GND") (pinfunction "GND_3-GND") (pintype "power_in"))
      (node (ref "LED4") (pin "3-GND") (pinfunction "GND_3-GND") (pintype "power_in"))
      (node (ref "LED40") (pin "3-GND") (pinfunction "GND_3-GND") (pintype "power_in"))
      (node (ref "LED41") (pin "3-GND") (pinfunction "GND_3-GND") (pintype "power_in"))
      (node (ref "LED42") (pin "3-GND") (pinfunction "GND_3-GND") (pintype "power_in"))
      (node (ref "LED43") (pin "3-GND") (pinfunction "GND_3-GND") (pintype "power_in"))
      (node (ref "LED44") (pin "3-GND") (pinfunction "GND_3-GND") (pintype "power_in"))
      (node (ref "LED45") (pin "3-GND") (pinfunction "GND_3-GND") (pintype "power_in"))
      (node (ref "LED46") (pin "3-GND") (pinfunction "GND_3-GND") (pintype "power_in"))
      (node (ref "LED47") (pin "3-GND") (pinfunction "GND_3-GND") (pintype "power_in"))
      (node (ref "LED48") (pin "3-GND") (pinfunction "GND_3-GND") (pintype "power_in"))
      (node (ref "LED49") (pin "3-GND") (pinfunction "GND_3-GND") (pintype "power_in"))
      (node (ref "LED5") (pin "3-GND") (pinfunction "GND_3-GND") (pintype "power_in"))
      (node (ref "LED50") (pin "3-GND") (pinfunction "GND_3-GND") (pintype "power_in"))
      (node (ref "LED51") (pin "3-GND") (pinfunction "GND_3-GND") (pintype "power_in"))
      (node (ref "LED52") (pin "3-GND") (pinfunction "GND_3-GND") (pintype "power_in"))
      (node (ref "LED53") (pin "3-GND") (pinfunction "GND_3-GND") (pintype "power_in"))
      (node (ref "LED54") (pin "3-GND") (pinfunction "GND_3-GND") (pintype "power_in"))
      (node (ref "LED55") (pin "3-GND") (pinfunction "GND_3-GND") (pintype "power_in"))
      (node (ref "LED56") (pin "3-GND") (pinfunction "GND_3-GND") (pintype "power_in"))
      (node (ref "LED57") (pin "3-GND") (pinfunction "GND_3-GND") (pintype "power_in"))
      (node (ref "LED58") (pin "3-GND") (pinfunction "GND_3-GND") (pintype "power_in"))
      (node (ref "LED59") (pin "3-GND") (pinfunction "GND_3-GND") (pintype "power_in"))
      (node (ref "LED6") (pin "3-GND") (pinfunction "GND_3-GND") (pintype "power_in"))
      (node (ref "LED60") (pin "3-GND") (pinfunction "GND_3-GND") (pintype "power_in"))
      (node (ref "LED61") (pin "3-GND") (pinfunction "GND_3-GND") (pintype "power_in"))
      (node (ref "LED62") (pin "3-GND") (pinfunction "GND_3-GND") (pintype "power_in"))
      (node (ref "LED63") (pin "3-GND") (pinfunction "GND_3-GND") (pintype "power_in"))
      (node (ref "LED64") (pin "3-GND") (pinfunction "GND_3-GND") (pintype "power_in"))
      (node (ref "LED65") (pin "3-GND") (pinfunction "GND_3-GND") (pintype "power_in"))
      (node (ref "LED66") (pin "3-GND") (pinfunction "GND_3-GND") (pintype "power_in"))
      (node (ref "LED67") (pin "3-GND") (pinfunction "GND_3-GND") (pintype "power_in"))
      (node (ref "LED68") (pin "3-GND") (pinfunction "GND_3-GND") (pintype "power_in"))
      (node (ref "LED69") (pin "3-GND") (pinfunction "GND_3-GND") (pintype "power_in"))
      (node (ref "LED7") (pin "3-GND") (pinfunction "GND_3-GND") (pintype "power_in"))
      (node (ref "LED70") (pin "3-GND") (pinfunction "GND_3-GND") (pintype "power_in"))
      (node (ref "LED71") (pin "3-GND") (pinfunction "GND_3-GND") (pintype "power_in"))
      (node (ref "LED72") (pin "3-GND") (pinfunction "GND_3-GND") (pintype "power_in"))
      (node (ref "LED73") (pin "3-GND") (pinfunction "GND_3-GND") (pintype "power_in"))
      (node (ref "LED74") (pin "3-GND") (pinfunction "GND_3-GND") (pintype "power_in"))
      (node (ref "LED75") (pin "3-GND") (pinfunction "GND_3-GND") (pintype "power_in"))
      (node (ref "LED76") (pin "3-GND") (pinfunction "GND_3-GND") (pintype "power_in"))
      (node (ref "LED77") (pin "3-GND") (pinfunction "GND_3-GND") (pintype "power_in"))
      (node (ref "LED78") (pin "3-GND") (pinfunction "GND_3-GND") (pintype "power_in"))
      (node (ref "LED79") (pin "3-GND") (pinfunction "GND_3-GND") (pintype "power_in"))
      (node (ref "LED8") (pin "3-GND") (pinfunction "GND_3-GND") (pintype "power_in"))
      (node (ref "LED80") (pin "3-GND") (pinfunction "GND_3-GND") (pintype "power_in"))
      (node (ref "LED81") (pin "3-GND") (pinfunction "GND_3-GND") (pintype "power_in"))
      (node (ref "LED82") (pin "3-GND") (pinfunction "GND_3-GND") (pintype "power_in"))
      (node (ref "LED83") (pin "3-GND") (pinfunction "GND_3-GND") (pintype "power_in"))
      (node (ref "LED84") (pin "3-GND") (pinfunction "GND_3-GND") (pintype "power_in"))
      (node (ref "LED85") (pin "3-GND") (pinfunction "GND_3-GND") (pintype "power_in"))
      (node (ref "LED86") (pin "3-GND") (pinfunction "GND_3-GND") (pintype "power_in"))
      (node (ref "LED87") (pin "3-GND") (pinfunction "GND_3-GND") (pintype "power_in"))
      (node (ref "LED88") (pin "3-GND") (pinfunction "GND_3-GND") (pintype "power_in"))
      (node (ref "LED89") (pin "3-GND") (pinfunction "GND_3-GND") (pintype "power_in"))
      (node (ref "LED9") (pin "3-GND") (pinfunction "GND_3-GND") (pintype "power_in"))
      (node (ref "LED90") (pin "3-GND") (pinfunction "GND_3-GND") (pintype "power_in"))
      (node (ref "LED91") (pin "3-GND") (pinfunction "GND_3-GND") (pintype "power_in"))
      (node (ref "LED92") (pin "3-GND") (pinfunction "GND_3-GND") (pintype "power_in"))
      (node (ref "LED93") (pin "3-GND") (pinfunction "GND_3-GND") (pintype "power_in"))
      (node (ref "LED94") (pin "3-GND") (pinfunction "GND_3-GND") (pintype "power_in"))
      (node (ref "LED95") (pin "3-GND") (pinfunction "GND_3-GND") (pintype "power_in"))
      (node (ref "LED96") (pin "3-GND") (pinfunction "GND_3-GND") (pintype "power_in"))
      (node (ref "LED97") (pin "3-GND") (pinfunction "GND_3-GND") (pintype "power_in"))
      (node (ref "LED98") (pin "3-GND") (pinfunction "GND_3-GND") (pintype "power_in"))
      (node (ref "LED99") (pin "3-GND") (pinfunction "GND_3-GND") (pintype "power_in"))
    )
    (net (code "3") (name "Net-(LED1-DO)") (class "Default")
      (node (ref "LED1") (pin "2-DOUT") (pinfunction "DO_2-DOUT") (pintype "output"))
      (node (ref "LED2") (pin "4-DIN") (pinfunction "DI_4-DIN") (pintype "input"))
    )
    (net (code "4") (name "Net-(LED2-DO)") (class "Default")
      (node (ref "LED2") (pin "2-DOUT") (pinfunction "DO_2-DOUT") (pintype "output"))
      (node (ref "LED3") (pin "4-DIN") (pinfunction "DI_4-DIN") (pintype "input"))
    )
    (net (code "5") (name "Net-(LED3-DO)") (class "Default")
      (node (ref "LED3") (pin "2-DOUT") (pinfunction "DO_2-DOUT") (pintype "output"))
      (node (ref "LED4") (pin "4-DIN") (pinfunction "DI_4-DIN") (pintype "input"))
    )
    (net (code "6") (name "Net-(LED4-DO)") (class "Default")
      (node (ref "LED4") (pin "2-DOUT") (pinfunction "DO_2-DOUT") (pintype "output"))
      (node (ref "LED5") (pin "4-DIN") (pinfunction "DI_4-DIN") (pintype "input"))
    )
    (net (code "7") (name "Net-(LED5-DO)") (class "Default")
      (node (ref "LED5") (pin "2-DOUT") (pinfunction "DO_2-DOUT") (pintype "output"))
      (node (ref "LED6") (pin "4-DIN") (pinfunction "DI_4-DIN") (pintype "input"))
    )
    (net (code "8") (name "Net-(LED6-DO)") (class "Default")
      (node (ref "LED6") (pin "2-DOUT") (pinfunction "DO_2-DOUT") (pintype "output"))
      (node (ref "LED7") (pin "4-DIN") (pinfunction "DI_4-DIN") (pintype "input"))
    )
    (net (code "9") (name "Net-(LED7-DO)") (class "Default")
      (node (ref "LED7") (pin "2-DOUT") (pinfunction "DO_2-DOUT") (pintype "output"))
      (node (ref "LED8") (pin "4-DIN") (pinfunction "DI_4-DIN") (pintype "input"))
    )
    (net (code "10") (name "Net-(LED8-DO)") (class "Default")
      (node (ref "LED8") (pin "2-DOUT") (pinfunction "DO_2-DOUT") (pintype "output"))
      (node (ref "LED9") (pin "4-DIN") (pinfunction "DI_4-DIN") (pintype "input"))
    )
    (net (code "11") (name "Net-(LED10-DI)") (class "Default")
      (node (ref "LED10") (pin "4-DIN") (pinfunction "DI_4-DIN") (pintype "input"))
      (node (ref "LED9") (pin "2-DOUT") (pinfunction "DO_2-DOUT") (pintype "output"))
    )
    (net (code "12") (name "Net-(LED10-DO)") (class "Default")
      (node (ref "LED10") (pin "2-DOUT") (pinfunction "DO_2-DOUT") (pintype "output"))
      (node (ref "LED11") (pin "4-DIN") (pinfunction "DI_4-DIN") (pintype "input"))
    )
    (net (code "13") (name "Net-(LED11-DO)") (class "Default")
      (node (ref "LED11") (pin "2-DOUT") (pinfunction "DO_2-DOUT") (pintype "output"))
      (node (ref "LED12") (pin "4-DIN") (pinfunction "DI_4-DIN") (pintype "input"))
    )
    (net (code "14") (name "Net-(LED12-DO)") (class "Default")
      (node (ref "LED12") (pin "2-DOUT") (pinfunction "DO_2-DOUT") (pintype "output"))
      (node (ref "LED13") (pin "4-DIN") (pinfunction "DI_4-DIN") (pintype "input"))
    )
    (net (code "15") (name "Net-(LED13-DO)") (class "Default")
      (node (ref "LED13") (pin "2-DOUT") (pinfunction "DO_2-DOUT") (pintype "output"))
      (node (ref "LED14") (pin "4-DIN") (pinfunction "DI_4-DIN") (pintype "input"))
    )
    (net (code "16") (name "Net-(LED14-DO)") (class "Default")
      (node (ref "LED14") (pin "2-DOUT") (pinfunction "DO_2-DOUT") (pintype "output"))
      (node (ref "LED15") (pin "4-DIN") (pinfunction "DI_4-DIN") (pintype "input"))
    )
    (net (code "17") (name "Net-(LED15-DO)") (class "Default")
      (node (ref "LED15") (pin "2-DOUT") (pinfunction "DO_2-DOUT") (pintype "output"))
      (node (ref "LED16") (pin "4-DIN") (pinfunction "DI_4-DIN") (pintype "input"))
    )
    (net (code "18") (name "Net-(LED16-DO)") (class "Default")
      (node (ref "LED16") (pin "2-DOUT") (pinfunction "DO_2-DOUT") (pintype "output"))
      (node (ref "LED17") (pin "4-DIN") (pinfunction "DI_4-DIN") (pintype "input"))
    )
    (net (code "19") (name "Net-(LED17-DO)") (class "Default")
      (node (ref "LED17") (pin "2-DOUT") (pinfunction "DO_2-DOUT") (pintype "output"))
      (node (ref "LED18") (pin "4-DIN") (pinfunction "DI_4-DIN") (pintype "input"))
    )
    (net (code "20") (name "Net-(LED18-DO)") (class "Default")
      (node (ref "LED18") (pin "2-DOUT") (pinfunction "DO_2-DOUT") (pintype "output"))
      (node (ref "LED19") (pin "4-DIN") (pinfunction "DI_4-DIN") (pintype "input"))
    )
    (net (code "21") (name "Net-(LED19-DO)") (class "Default")
      (node (ref "LED19") (pin "2-DOUT") (pinfunction "DO_2-DOUT") (pintype "output"))
      (node (ref "LED20") (pin "4-DIN") (pinfunction "DI_4-DIN") (pintype "input"))
    )
    (net (code "22") (name "Net-(LED20-DO)") (class "Default")
      (node (ref "LED20") (pin "2-DOUT") (pinfunction "DO_2-DOUT") (pintype "output"))
      (node (ref "LED21") (pin "4-DIN") (pinfunction "DI_4-DIN") (pintype "input"))
    )
    (net (code "23") (name "Net-(LED21-DO)") (class "Default")
      (node (ref "LED21") (pin "2-DOUT") (pinfunction "DO_2-DOUT") (pintype "output"))
      (node (ref "LED22") (pin "4-DIN") (pinfunction "DI_4-DIN") (pintype "input"))
    )
    (net (code "24") (name "Net-(LED22-DO)") (class "Default")
      (node (ref "LED22") (pin "2-DOUT") (pinfunction "DO_2-DOUT") (pintype "output"))
      (node (ref "LED23") (pin "4-DIN") (pinfunction "DI_4-DIN") (pintype "input"))
    )
    (net (code "25") (name "Net-(LED23-DO)") (class "Default")
      (node (ref "LED23") (pin "2-DOUT") (pinfunction "DO_2-DOUT") (pintype "output"))
      (node (ref "LED24") (pin "4-DIN") (pinfunction "DI_4-DIN") (pintype "input"))
    )
    (net (code "26") (name "Net-(LED24-DO)") (class "Default")
      (node (ref "LED24") (pin "2-DOUT") (pinfunction "DO_2-DOUT") (pintype "output"))
      (node (ref "LED25") (pin "4-DIN") (pinfunction "DI_4-DIN") (pintype "input"))
    )
    (net (code "27") (name "Net-(LED25-DO)") (class "Default")
      (node (ref "LED25") (pin "2-DOUT") (pinfunction "DO_2-DOUT") (pintype "output"))
      (node (ref "LED26") (pin "4-DIN") (pinfunction "DI_4-DIN") (pintype "input"))
    )
    (net (code "28") (name "Net-(LED26-DO)") (class "Default")
      (node (ref "LED26") (pin "2-DOUT") (pinfunction "DO_2-DOUT") (pintype "output"))
      (node (ref "LED27") (pin "4-DIN") (pinfunction "DI_4-DIN") (pintype "input"))
    )
    (net (code "29") (name "Net-(LED27-DO)") (class "Default")
      (node (ref "LED27") (pin "2-DOUT") (pinfunction "DO_2-DOUT") (pintype "output"))
      (node (ref "LED28") (pin "4-DIN") (pinfunction "DI_4-DIN") (pintype "input"))
    )
    (net (code "30") (name "Net-(LED28-DO)") (class "Default")
      (node (ref "LED28") (pin "2-DOUT") (pinfunction "DO_2-DOUT") (pintype "output"))
      (node (ref "LED29") (pin "4-DIN") (pinfunction "DI_4-DIN") (pintype "input"))
    )
    (net (code "31") (name "Net-(LED29-DO)") (class "Default")
      (node (ref "LED29") (pin "2-DOUT") (pinfunction "DO_2-DOUT") (pintype "output"))
      (node (ref "LED30") (pin "4-DIN") (pinfunction "DI_4-DIN") (pintype "input"))
    )
    (net (code "32") (name "Net-(LED30-DO)") (class "Default")
      (node (ref "LED30") (pin "2-DOUT") (pinfunction "DO_2-DOUT") (pintype "output"))
      (node (ref "LED31") (pin "4-DIN") (pinfunction "DI_4-DIN") (pintype "input"))
    )
    (net (code "33") (name "Net-(LED31-DO)") (class "Default")
      (node (ref "LED31") (pin "2-DOUT") (pinfunction "DO_2-DOUT") (pintype "output"))
      (node (ref "LED32") (pin "4-DIN") (pinfunction "DI_4-DIN") (pintype "input"))
    )
    (net (code "34") (name "Net-(LED32-DO)") (class "Default")
      (node (ref "LED32") (pin "2-DOUT") (pinfunction "DO_2-DOUT") (pintype "output"))
      (node (ref "LED33") (pin "4-DIN") (pinfunction "DI_4-DIN") (pintype "input"))
    )
    (net (code "35") (name "Net-(LED33-DO)") (class "Default")
      (node (ref "LED33") (pin "2-DOUT") (pinfunction "DO_2-DOUT") (pintype "output"))
      (node (ref "LED34") (pin "4-DIN") (pinfunction "DI_4-DIN") (pintype "input"))
    )
    (net (code "36") (name "Net-(LED34-DO)") (class "Default")
      (node (ref "LED34") (pin "2-DOUT") (pinfunction "DO_2-DOUT") (pintype "output"))
      (node (ref "LED35") (pin "4-DIN") (pinfunction "DI_4-DIN") (pintype "input"))
    )
    (net (code "37") (name "Net-(LED35-DO)") (class "Default")
      (node (ref "LED35") (pin "2-DOUT") (pinfunction "DO_2-DOUT") (pintype "output"))
      (node (ref "LED36") (pin "4-DIN") (pinfunction "DI_4-DIN") (pintype "input"))
    )
    (net (code "38") (name "Net-(LED36-DO)") (class "Default")
      (node (ref "LED36") (pin "2-DOUT") (pinfunction "DO_2-DOUT") (pintype "output"))
      (node (ref "LED37") (pin "4-DIN") (pinfunction "DI_4-DIN") (pintype "input"))
    )
    (net (code "39") (name "Net-(LED37-DO)") (class "Default")
      (node (ref "LED37") (pin "2-DOUT") (pinfunction "DO_2-DOUT") (pintype "output"))
      (node (ref "LED38") (pin "4-DIN") (pinfunction "DI_4-DIN") (pintype "input"))
    )
    (net (code "40") (name "Net-(LED38-DO)") (class "Default")
      (node (ref "LED38") (pin "2-DOUT") (pinfunction "DO_2-DOUT") (pintype "output"))
      (node (ref "LED39") (pin "4-DIN") (pinfunction "DI_4-DIN") (pintype "input"))
    )
    (net (code "41") (name "Net-(LED39-DO)") (class "Default")
      (node (ref "LED39") (pin "2-DOUT") (pinfunction "DO_2-DOUT") (pintype "output"))
      (node (ref "LED40") (pin "4-DIN") (pinfunction "DI_4-DIN") (pintype "input"))
    )
    (net (code "42") (name "Net-(LED40-DO)") (class "Default")
      (node (ref "LED40") (pin "2-DOUT") (pinfunction "DO_2-DOUT") (pintype "output"))
      (node (ref "LED41") (pin "4-DIN") (pinfunction "DI_4-DIN") (pintype "input"))
    )
    (net (code "43") (name "Net-(LED41-DO)") (class "Default")
      (node (ref "LED41") (pin "2-DOUT") (pinfunction "DO_2-DOUT") (pintype "output"))
      (node (ref "LED42") (pin "4-DIN") (pinfunction "DI_4-DIN") (pintype "input"))
    )
    (net (code "44") (name "Net-(LED42-DO)") (class "Default")
      (node (ref "LED42") (pin "2-DOUT") (pinfunction "DO_2-DOUT") (pintype "output"))
      (node (ref "LED43") (pin "4-DIN") (pinfunction "DI_4-DIN") (pintype "input"))
    )
    (net (code "45") (name "Net-(LED43-DO)") (class "Default")
      (node (ref "LED43") (pin "2-DOUT") (pinfunction "DO_2-DOUT") (pintype "output"))
      (node (ref "LED44") (pin "4-DIN") (pinfunction "DI_4-DIN") (pintype "input"))
    )
    (net (code "46") (name "Net-(LED44-DO)") (class "Default")
      (node (ref "LED44") (pin "2-DOUT") (pinfunction "DO_2-DOUT") (pintype "output"))
      (node (ref "LED45") (pin "4-DIN") (pinfunction "DI_4-DIN") (pintype "input"))
    )
    (net (code "47") (name "Net-(LED45-DO)") (class "Default")
      (node (ref "LED45") (pin "2-DOUT") (pinfunction "DO_2-DOUT") (pintype "output"))
      (node (ref "LED46") (pin "4-DIN") (pinfunction "DI_4-DIN") (pintype "input"))
    )
    (net (code "48") (name "Net-(LED46-DO)") (class "Default")
      (node (ref "LED46") (pin "2-DOUT") (pinfunction "DO_2-DOUT") (pintype "output"))
      (node (ref "LED47") (pin "4-DIN") (pinfunction "DI_4-DIN") (pintype "input"))
    )
    (net (code "49") (name "Net-(LED47-DO)") (class "Default")
      (node (ref "LED47") (pin "2-DOUT") (pinfunction "DO_2-DOUT") (pintype "output"))
      (node (ref "LED48") (pin "4-DIN") (pinfunction "DI_4-DIN") (pintype "input"))
    )
    (net (code "50") (name "Net-(LED48-DO)") (class "Default")
      (node (ref "LED48") (pin "2-DOUT") (pinfunction "DO_2-DOUT") (pintype "output"))
      (node (ref "LED49") (pin "4-DIN") (pinfunction "DI_4-DIN") (pintype "input"))
    )
    (net (code "51") (name "Net-(LED49-DO)") (class "Default")
      (node (ref "LED49") (pin "2-DOUT") (pinfunction "DO_2-DOUT") (pintype "output"))
      (node (ref "LED50") (pin "4-DIN") (pinfunction "DI_4-DIN") (pintype "input"))
    )
    (net (code "52") (name "Net-(LED50-DO)") (class "Default")
      (node (ref "LED50") (pin "2-DOUT") (pinfunction "DO_2-DOUT") (pintype "output"))
      (node (ref "LED51") (pin "4-DIN") (pinfunction "DI_4-DIN") (pintype "input"))
    )
    (net (code "53") (name "Net-(LED51-DO)") (class "Default")
      (node (ref "LED51") (pin "2-DOUT") (pinfunction "DO_2-DOUT") (pintype "output"))
      (node (ref "LED52") (pin "4-DIN") (pinfunction "DI_4-DIN") (pintype "input"))
    )
    (net (code "54") (name "Net-(LED52-DO)") (class "Default")
      (node (ref "LED52") (pin "2-DOUT") (pinfunction "DO_2-DOUT") (pintype "output"))
      (node (ref "LED53") (pin "4-DIN") (pinfunction "DI_4-DIN") (pintype "input"))
    )
    (net (code "55") (name "Net-(LED53-DO)") (class "Default")
      (node (ref "LED53") (pin "2-DOUT") (pinfunction "DO_2-DOUT") (pintype "output"))
      (node (ref "LED54") (pin "4-DIN") (pinfunction "DI_4-DIN") (pintype "input"))
    )
    (net (code "56") (name "Net-(LED54-DO)") (class "Default")
      (node (ref "LED54") (pin "2-DOUT") (pinfunction "DO_2-DOUT") (pintype "output"))
      (node (ref "LED55") (pin "4-DIN") (pinfunction "DI_4-DIN") (pintype "input"))
    )
    (net (code "57") (name "Net-(LED55-DO)") (class "Default")
      (node (ref "LED55") (pin "2-DOUT") (pinfunction "DO_2-DOUT") (pintype "output"))
      (node (ref "LED56") (pin "4-DIN") (pinfunction "DI_4-DIN") (pintype "input"))
    )
    (net (code "58") (name "Net-(LED56-DO)") (class "Default")
      (node (ref "LED56") (pin "2-DOUT") (pinfunction "DO_2-DOUT") (pintype "output"))
      (node (ref "LED57") (pin "4-DIN") (pinfunction "DI_4-DIN") (pintype "input"))
    )
    (net (code "59") (name "Net-(LED57-DO)") (class "Default")
      (node (ref "LED57") (pin "2-DOUT") (pinfunction "DO_2-DOUT") (pintype "output"))
      (node (ref "LED58") (pin "4-DIN") (pinfunction "DI_4-DIN") (pintype "input"))
    )
    (net (code "60") (name "Net-(LED58-DO)") (class "Default")
      (node (ref "LED58") (pin "2-DOUT") (pinfunction "DO_2-DOUT") (pintype "output"))
      (node (ref "LED59") (pin "4-DIN") (pinfunction "DI_4-DIN") (pintype "input"))
    )
    (net (code "61") (name "Net-(LED59-DO)") (class "Default")
      (node (ref "LED59") (pin "2-DOUT") (pinfunction "DO_2-DOUT") (pintype "output"))
      (node (ref "LED60") (pin "4-DIN") (pinfunction "DI_4-DIN") (pintype "input"))
    )
    (net (code "62") (name "Net-(LED60-DO)") (class "Default")
      (node (ref "LED60") (pin "2-DOUT") (pinfunction "DO_2-DOUT") (pintype "output"))
      (node (ref "LED61") (pin "4-DIN") (pinfunction "DI_4-DIN") (pintype "input"))
    )
    (net (code "63") (name "Net-(LED61-DO)") (class "Default")
      (node (ref "LED61") (pin "2-DOUT") (pinfunction "DO_2-DOUT") (pintype "output"))
      (node (ref "LED62") (pin "4-DIN") (pinfunction "DI_4-DIN") (pintype "input"))
    )
    (net (code "64") (name "Net-(LED62-DO)") (class "Default")
      (node (ref "LED62") (pin "2-DOUT") (pinfunction "DO_2-DOUT") (pintype "output"))
      (node (ref "LED63") (pin "4-DIN") (pinfunction "DI_4-DIN") (pintype "input"))
    )
    (net (code "65") (name "Net-(LED63-DO)") (class "Default")
      (node (ref "LED63") (pin "2-DOUT") (pinfunction "DO_2-DOUT") (pintype "output"))
      (node (ref "LED64") (pin "4-DIN") (pinfunction "DI_4-DIN") (pintype "input"))
    )
    (net (code "66") (name "Net-(LED64-DO)") (class "Default")
      (node (ref "LED64") (pin "2-DOUT") (pinfunction "DO_2-DOUT") (pintype "output"))
      (node (ref "LED65") (pin "4-DIN") (pinfunction "DI_4-DIN") (pintype "input"))
    )
    (net (code "67") (name "Net-(LED65-DO)") (class "Default")
      (node (ref "LED65") (pin "2-DOUT") (pinfunction "DO_2-DOUT") (pintype "output"))
      (node (ref "LED66") (pin "4-DIN") (pinfunction "DI_4-DIN") (pintype "input"))
    )
    (net (code "68") (name "Net-(LED66-DO)") (class "Default")
      (node (ref "LED66") (pin "2-DOUT") (pinfunction "DO_2-DOUT") (pintype "output"))
      (node (ref "LED67") (pin "4-DIN") (pinfunction "DI_4-DIN") (pintype "input"))
    )
    (net (code "69") (name "Net-(LED67-DO)") (class "Default")
      (node (ref "LED67") (pin "2-DOUT") (pinfunction "DO_2-DOUT") (pintype "output"))
      (node (ref "LED68") (pin "4-DIN") (pinfunction "DI_4-DIN") (pintype "input"))
    )
    (net (code "70") (name "Net-(LED68-DO)") (class "Default")
      (node (ref "LED68") (pin "2-DOUT") (pinfunction "DO_2-DOUT") (pintype "output"))
      (node (ref "LED69") (pin "4-DIN") (pinfunction "DI_4-DIN") (pintype "input"))
    )
    (net (code "71") (name "Net-(LED69-DO)") (class "Default")
      (node (ref "LED69") (pin "2-DOUT") (pinfunction "DO_2-DOUT") (pintype "output"))
      (node (ref "LED70") (pin "4-DIN") (pinfunction "DI_4-DIN") (pintype "input"))
    )
    (net (code "72") (name "Net-(LED70-DO)") (class "Default")
      (node (ref "LED70") (pin "2-DOUT") (pinfunction "DO_2-DOUT") (pintype "output"))
      (node (ref "LED71") (pin "4-DIN") (pinfunction "DI_4-DIN") (pintype "input"))
    )
    (net (code "73") (name "Net-(LED71-DO)") (class "Default")
      (node (ref "LED71") (pin "2-DOUT") (pinfunction "DO_2-DOUT") (pintype "output"))
      (node (ref "LED72") (pin "4-DIN") (pinfunction "DI_4-DIN") (pintype "input"))
    )
    (net (code "74") (name "Net-(LED72-DO)") (class "Default")
      (node (ref "LED72") (pin "2-DOUT") (pinfunction "DO_2-DOUT") (pintype "output"))
      (node (ref "LED73") (pin "4-DIN") (pinfunction "DI_4-DIN") (pintype "input"))
    )
    (net (code "75") (name "Net-(LED73-DO)") (class "Default")
      (node (ref "LED73") (pin "2-DOUT") (pinfunction "DO_2-DOUT") (pintype "output"))
      (node (ref "LED74") (pin "4-DIN") (pinfunction "DI_4-DIN") (pintype "input"))
    )
    (net (code "76") (name "Net-(LED74-DO)") (class "Default")
      (node (ref "LED74") (pin "2-DOUT") (pinfunction "DO_2-DOUT") (pintype "output"))
      (node (ref "LED75") (pin "4-DIN") (pinfunction "DI_4-DIN") (pintype "input"))
    )
    (net (code "77") (name "Net-(LED75-DO)") (class "Default")
      (node (ref "LED75") (pin "2-DOUT") (pinfunction "DO_2-DOUT") (pintype "output"))
      (node (ref "LED76") (pin "4-DIN") (pinfunction "DI_4-DIN") (pintype "input"))
    )
    (net (code "78") (name "Net-(LED76-DO)") (class "Default")
      (node (ref "LED76") (pin "2-DOUT") (pinfunction "DO_2-DOUT") (pintype "output"))
      (node (ref "LED77") (pin "4-DIN") (pinfunction "DI_4-DIN") (pintype "input"))
    )
    (net (code "79") (name "Net-(LED77-DO)") (class "Default")
      (node (ref "LED77") (pin "2-DOUT") (pinfunction "DO_2-DOUT") (pintype "output"))
      (node (ref "LED78") (pin "4-DIN") (pinfunction "DI_4-DIN") (pintype "input"))
    )
    (net (code "80") (name "Net-(LED78-DO)") (class "Default")
      (node (ref "LED78") (pin "2-DOUT") (pinfunction "DO_2-DOUT") (pintype "output"))
      (node (ref "LED79") (pin "4-DIN") (pinfunction "DI_4-DIN") (pintype "input"))
    )
    (net (code "81") (name "Net-(LED79-DO)") (class "Default")
      (node (ref "LED79") (pin "2-DOUT") (pinfunction "DO_2-DOUT") (pintype "output"))
      (node (ref "LED80") (pin "4-DIN") (pinfunction "DI_4-DIN") (pintype "input"))
    )
    (net (code "82") (name "Net-(LED80-DO)") (class "Default")
      (node (ref "LED80") (pin "2-DOUT") (pinfunction "DO_2-DOUT") (pintype "output"))
      (node (ref "LED81") (pin "4-DIN") (pinfunction "DI_4-DIN") (pintype "input"))
    )
    (net (code "83") (name "Net-(LED81-DO)") (class "Default")
      (node (ref "LED81") (pin "2-DOUT") (pinfunction "DO_2-DOUT") (pintype "output"))
      (node (ref "LED82") (pin "4-DIN") (pinfunction "DI_4-DIN") (pintype "input"))
    )
    (net (code "84") (name "Net-(LED82-DO)") (class "Default")
      (node (ref "LED82") (pin "2-DOUT") (pinfunction "DO_2-DOUT") (pintype "output"))
      (node (ref "LED83") (pin "4-DIN") (pinfunction "DI_4-DIN") (pintype "input"))
    )
    (net (code "85") (name "Net-(LED83-DO)") (class "Default")
      (node (ref "LED83") (pin "2-DOUT") (pinfunction "DO_2-DOUT") (pintype "output"))
      (node (ref "LED84") (pin "4-DIN") (pinfunction "DI_4-DIN") (pintype "input"))
    )
    (net (code "86") (name "Net-(LED84-DO)") (class "Default")
      (node (ref "LED84") (pin "2-DOUT") (pinfunction "DO_2-DOUT") (pintype "output"))
      (node (ref "LED85") (pin "4-DIN") (pinfunction "DI_4-DIN") (pintype "input"))
    )
    (net (code "87") (name "Net-(LED85-DO)") (class "Default")
      (node (ref "LED85") (pin "2-DOUT") (pinfunction "DO_2-DOUT") (pintype "output"))
      (node (ref "LED86") (pin "4-DIN") (pinfunction "DI_4-DIN") (pintype "input"))
    )
    (net (code "88") (name "Net-(LED86-DO)") (class "Default")
      (node (ref "LED86") (pin "2-DOUT") (pinfunction "DO_2-DOUT") (pintype "output"))
      (node (ref "LED87") (pin "4-DIN") (pinfunction "DI_4-DIN") (pintype "input"))
    )
    (net (code "89") (name "Net-(LED87-DO)") (class "Default")
      (node (ref "LED87") (pin "2-DOUT") (pinfunction "DO_2-DOUT") (pintype "output"))
      (node (ref "LED88") (pin "4-DIN") (pinfunction "DI_4-DIN") (pintype "input"))
    )
    (net (code "90") (name "Net-(LED88-DO)") (class "Default")
      (node (ref "LED88") (pin "2-DOUT") (pinfunction "DO_2-DOUT") (pintype "output"))
      (node (ref "LED89") (pin "4-DIN") (pinfunction "DI_4-DIN") (pintype "input"))
    )
    (net (code "91") (name "Net-(LED89-DO)") (class "Default")
      (node (ref "LED89") (pin "2-DOUT") (pinfunction "DO_2-DOUT") (pintype "output"))
      (node (ref "LED90") (pin "4-DIN") (pinfunction "DI_4-DIN") (pintype "input"))
    )
    (net (code "92") (name "Net-(LED90-DO)") (class "Default")
      (node (ref "LED90") (pin "2-DOUT") (pinfunction "DO_2-DOUT") (pintype "output"))
      (node (ref "LED91") (pin "4-DIN") (pinfunction "DI_4-DIN") (pintype "input"))
    )
    (net (code "93") (name "Net-(LED91-DO)") (class "Default")
      (node (ref "LED91") (pin "2-DOUT") (pinfunction "DO_2-DOUT") (pintype "output"))
      (node (ref "LED92") (pin "4-DIN") (pinfunction "DI_4-DIN") (pintype "input"))
    )
    (net (code "94") (name "Net-(LED92-DO)") (class "Default")
      (node (ref "LED92") (pin "2-DOUT") (pinfunction "DO_2-DOUT") (pintype "output"))
      (node (ref "LED93") (pin "4-DIN") (pinfunction "DI_4-DIN") (pintype "input"))
    )
    (net (code "95") (name "Net-(LED93-DO)") (class "Default")
      (node (ref "LED93") (pin "2-DOUT") (pinfunction "DO_2-DOUT") (pintype "output"))
      (node (ref "LED94") (pin "4-DIN") (pinfunction "DI_4-DIN") (pintype "input"))
    )
    (net (code "96") (name "Net-(LED94-DO)") (class "Default")
      (node (ref "LED94") (pin "2-DOUT") (pinfunction "DO_2-DOUT") (pintype "output"))
      (node (ref "LED95") (pin "4-DIN") (pinfunction "DI_4-DIN") (pintype "input"))
    )
    (net (code "97") (name "Net-(LED95-DO)") (class "Default")
      (node (ref "LED95") (pin "2-DOUT") (pinfunction "DO_2-DOUT") (pintype "output"))
      (node (ref "LED96") (pin "4-DIN") (pinfunction "DI_4-DIN") (pintype "input"))
    )
    (net (code "98") (name "Net-(LED96-DO)") (class "Default")
      (node (ref "LED96") (pin "2-DOUT") (pinfunction "DO_2-DOUT") (pintype "output"))
      (node (ref "LED97") (pin "4-DIN") (pinfunction "DI_4-DIN") (pintype "input"))
    )
    (net (code "99") (name "Net-(LED97-DO)") (class "Default")
      (node (ref "LED97") (pin "2-DOUT") (pinfunction "DO_2-DOUT") (pintype "output"))
      (node (ref "LED98") (pin "4-DIN") (pinfunction "DI_4-DIN") (pintype "input"))
    )
    (net (code "100") (name "Net-(LED98-DO)") (class "Default")
      (node (ref "LED98") (pin "2-DOUT") (pinfunction "DO_2-DOUT") (pintype "output"))
      (node (ref "LED99") (pin "4-DIN") (pinfunction "DI_4-DIN") (pintype "input"))
    )
    (net (code "101") (name "Net-(LED100-DI)") (class "Default")
      (node (ref "LED100") (pin "4-DIN") (pinfunction "DI_4-DIN") (pintype "input"))
      (node (ref "LED99") (pin "2-DOUT") (pinfunction "DO_2-DOUT") (pintype "output"))
    )
    (net (code "102") (name "Net-(LED100-DO)") (class "Default")
      (node (ref "LED100") (pin "2-DOUT") (pinfunction "DO_2-DOUT") (pintype "output"))
      (node (ref "LED101") (pin "4-DIN") (pinfunction "DI_4-DIN") (pintype "input"))
    )
    (net (code "103") (name "Net-(LED101-DO)") (class "Default")
      (node (ref "LED101") (pin "2-DOUT") (pinfunction "DO_2-DOUT") (pintype "output"))
      (node (ref "LED102") (pin "4-DIN") (pinfunction "DI_4-DIN") (pintype "input"))
    )
    (net (code "104") (name "Net-(LED102-DO)") (class "Default")
      (node (ref "LED102") (pin "2-DOUT") (pinfunction "DO_2-DOUT") (pintype "output"))
      (node (ref "LED103") (pin "4-DIN") (pinfunction "DI_4-DIN") (pintype "input"))
    )
    (net (code "105") (name "Net-(LED103-DO)") (class "Default")
      (node (ref "LED103") (pin "2-DOUT") (pinfunction "DO_2-DOUT") (pintype "output"))
      (node (ref "LED104") (pin "4-DIN") (pinfunction "DI_4-DIN") (pintype "input"))
    )
    (net (code "106") (name "Net-(LED104-DO)") (class "Default")
      (node (ref "LED104") (pin "2-DOUT") (pinfunction "DO_2-DOUT") (pintype "output"))
      (node (ref "LED105") (pin "4-DIN") (pinfunction "DI_4-DIN") (pintype "input"))
    )
    (net (code "107") (name "Net-(LED105-DO)") (class "Default")
      (node (ref "LED105") (pin "2-DOUT") (pinfunction "DO_2-DOUT") (pintype "output"))
      (node (ref "LED106") (pin "4-DIN") (pinfunction "DI_4-DIN") (pintype "input"))
    )
    (net (code "108") (name "Net-(LED106-DO)") (class "Default")
      (node (ref "LED106") (pin "2-DOUT") (pinfunction "DO_2-DOUT") (pintype "output"))
      (node (ref "LED107") (pin "4-DIN") (pinfunction "DI_4-DIN") (pintype "input"))
    )
    (net (code "109") (name "Net-(LED107-DO)") (class "Default")
      (node (ref "LED107") (pin "2-DOUT") (pinfunction "DO_2-DOUT") (pintype "output"))
      (node (ref "LED108") (pin "4-DIN") (pinfunction "DI_4-DIN") (pintype "input"))
    )
    (net (code "110") (name "Net-(LED108-DO)") (class "Default")
      (node (ref "LED108") (pin "2-DOUT") (pinfunction "DO_2-DOUT") (pintype "output"))
      (node (ref "LED109") (pin "4-DIN") (pinfunction "DI_4-DIN") (pintype "input"))
    )
    (net (code "111") (name "Net-(LED109-DO)") (class "Default")
      (node (ref "LED109") (pin "2-DOUT") (pinfunction "DO_2-DOUT") (pintype "output"))
      (node (ref "LED110") (pin "4-DIN") (pinfunction "DI_4-DIN") (pintype "input"))
    )
    (net (code "112") (name "Net-(LED110-DO)") (class "Default")
      (node (ref "LED110") (pin "2-DOUT") (pinfunction "DO_2-DOUT") (pintype "output"))
      (node (ref "LED111") (pin "4-DIN") (pinfunction "DI_4-DIN") (pintype "input"))
    )
    (net (code "113") (name "Net-(LED111-DO)") (class "Default")
      (node (ref "LED111") (pin "2-DOUT") (pinfunction "DO_2-DOUT") (pintype "output"))
      (node (ref "LED112") (pin "4-DIN") (pinfunction "DI_4-DIN") (pintype "input"))
    )
    (net (code "114") (name "Net-(LED112-DO)") (class "Default")
      (node (ref "LED112") (pin "2-DOUT") (pinfunction "DO_2-DOUT") (pintype "output"))
      (node (ref "LED113") (pin "4-DIN") (pinfunction "DI_4-DIN") (pintype "input"))
    )
    (net (code "115") (name "Net-(LED113-DO)") (class "Default")
      (node (ref "LED113") (pin "2-DOUT") (pinfunction "DO_2-DOUT") (pintype "output"))
      (node (ref "LED114") (pin "4-DIN") (pinfunction "DI_4-DIN") (pintype "input"))
    )
    (net (code "116") (name "Net-(LED114-DO)") (class "Default")
      (node (ref "LED114") (pin "2-DOUT") (pinfunction "DO_2-DOUT") (pintype "output"))
      (node (ref "LED115") (pin "4-DIN") (pinfunction "DI_4-DIN") (pintype "input"))
    )
    (net (code "117") (name "Net-(LED115-DO)") (class "Default")
      (node (ref "LED115") (pin "2-DOUT") (pinfunction "DO_2-DOUT") (pintype "output"))
      (node (ref "LED116") (pin "4-DIN") (pinfunction "DI_4-DIN") (pintype "input"))
    )
    (net (code "118") (name "Net-(LED116-DO)") (class "Default")
      (node (ref "LED116") (pin "2-DOUT") (pinfunction "DO_2-DOUT") (pintype "output"))
      (node (ref "LED117") (pin "4-DIN") (pinfunction "DI_4-DIN") (pintype "input"))
    )
    (net (code "119") (name "Net-(LED117-DO)") (class "Default")
      (node (ref "LED117") (pin "2-DOUT") (pinfunction "DO_2-DOUT") (pintype "output"))
      (node (ref "LED118") (pin "4-DIN") (pinfunction "DI_4-DIN") (pintype "input"))
    )
    (net (code "120") (name "Net-(LED118-DO)") (class "Default")
      (node (ref "LED118") (pin "2-DOUT") (pinfunction "DO_2-DOUT") (pintype "output"))
      (node (ref "LED119") (pin "4-DIN") (pinfunction "DI_4-DIN") (pintype "input"))
    )
    (net (code "121") (name "Net-(LED119-DO)") (class "Default")
      (node (ref "LED119") (pin "2-DOUT") (pinfunction "DO_2-DOUT") (pintype "output"))
      (node (ref "LED120") (pin "4-DIN") (pinfunction "DI_4-DIN") (pintype "input"))
    )
    (net (code "122") (name "Net-(LED120-DO)") (class "Default")
      (node (ref "LED120") (pin "2-DOUT") (pinfunction "DO_2-DOUT") (pintype "output"))
      (node (ref "LED121") (pin "4-DIN") (pinfunction "DI_4-DIN") (pintype "input"))
    )
    (net (code "123") (name "Net-(LED121-DO)") (class "Default")
      (node (ref "LED121") (pin "2-DOUT") (pinfunction "DO_2-DOUT") (pintype "output"))
      (node (ref "LED122") (pin "4-DIN") (pinfunction "DI_4-DIN") (pintype "input"))
    )
    (net (code "124") (name "Net-(LED122-DO)") (class "Default")
      (node (ref "LED122") (pin "2-DOUT") (pinfunction "DO_2-DOUT") (pintype "output"))
      (node (ref "LED123") (pin "4-DIN") (pinfunction "DI_4-DIN") (pintype "input"))
    )
    (net (code "125") (name "Net-(LED123-DO)") (class "Default")
      (node (ref "LED123") (pin "2-DOUT") (pinfunction "DO_2-DOUT") (pintype "output"))
      (node (ref "LED124") (pin "4-DIN") (pinfunction "DI_4-DIN") (pintype "input"))
    )
    (net (code "126") (name "Net-(LED124-DO)") (class "Default")
      (node (ref "LED124") (pin "2-DOUT") (pinfunction "DO_2-DOUT") (pintype "output"))
      (node (ref "LED125") (pin "4-DIN") (pinfunction "DI_4-DIN") (pintype "input"))
    )
    (net (code "127") (name "Net-(LED125-DO)") (class "Default")
      (node (ref "LED125") (pin "2-DOUT") (pinfunction "DO_2-DOUT") (pintype "output"))
      (node (ref "LED126") (pin "4-DIN") (pinfunction "DI_4-DIN") (pintype "input"))
    )
    (net (code "128") (name "Net-(LED126-DO)") (class "Default")
      (node (ref "LED126") (pin "2-DOUT") (pinfunction "DO_2-DOUT") (pintype "output"))
      (node (ref "LED127") (pin "4-DIN") (pinfunction "DI_4-DIN") (pintype "input"))
    )
    (net (code "129") (name "Net-(LED127-DO)") (class "Default")
      (node (ref "LED127") (pin "2-DOUT") (pinfunction "DO_2-DOUT") (pintype "output"))
      (node (ref "LED128") (pin "4-DIN") (pinfunction "DI_4-DIN") (pintype "input"))
    )
    (net (code "130") (name "Net-(LED128-DO)") (class "Default")
      (node (ref "LED128") (pin "2-DOUT") (pinfunction "DO_2-DOUT") (pintype "output"))
      (node (ref "LED129") (pin "4-DIN") (pinfunction "DI_4-DIN") (pintype "input"))
    )
    (net (code "131") (name "Net-(LED129-DO)") (class "Default")
      (node (ref "LED129") (pin "2-DOUT") (pinfunction "DO_2-DOUT") (pintype "output"))
      (node (ref "LED130") (pin "4-DIN") (pinfunction "DI_4-DIN") (pintype "input"))
    )
    (net (code "132") (name "Net-(LED130-DO)") (class "Default")
      (node (ref "LED130") (pin "2-DOUT") (pinfunction "DO_2-DOUT") (pintype "output"))
      (node (ref "LED131") (pin "4-DIN") (pinfunction "DI_4-DIN") (pintype "input"))
    )
    (net (code "133") (name "Net-(LED131-DO)") (class "Default")
      (node (ref "LED131") (pin "2-DOUT") (pinfunction "DO_2-DOUT") (pintype "output"))
      (node (ref "LED132") (pin "4-DIN") (pinfunction "DI_4-DIN") (pintype "input"))
    )
    (net (code "134") (name "Net-(LED132-DO)") (class "Default")
      (node (ref "LED132") (pin "2-DOUT") (pinfunction "DO_2-DOUT") (pintype "output"))
      (node (ref "LED133") (pin "4-DIN") (pinfunction "DI_4-DIN") (pintype "input"))
    )
    (net (code "135") (name "Net-(LED133-DO)") (class "Default")
      (node (ref "LED133") (pin "2-DOUT") (pinfunction "DO_2-DOUT") (pintype "output"))
      (node (ref "LED134") (pin "4-DIN") (pinfunction "DI_4-DIN") (pintype "input"))
    )
    (net (code "136") (name "Net-(LED134-DO)") (class "Default")
      (node (ref "LED134") (pin "2-DOUT") (pinfunction "DO_2-DOUT") (pintype "output"))
      (node (ref "LED135") (pin "4-DIN") (pinfunction "DI_4-DIN") (pintype "input"))
    )
    (net (code "137") (name "Net-(LED135-DO)") (class "Default")
      (node (ref "LED135") (pin "2-DOUT") (pinfunction "DO_2-DOUT") (pintype "output"))
      (node (ref "LED136") (pin "4-DIN") (pinfunction "DI_4-DIN") (pintype "input"))
    )
    (net (code "138") (name "Net-(LED136-DO)") (class "Default")
      (node (ref "LED136") (pin "2-DOUT") (pinfunction "DO_2-DOUT") (pintype "output"))
      (node (ref "LED137") (pin "4-DIN") (pinfunction "DI_4-DIN") (pintype "input"))
    )
    (net (code "139") (name "Net-(LED137-DO)") (class "Default")
      (node (ref "LED137") (pin "2-DOUT") (pinfunction "DO_2-DOUT") (pintype "output"))
      (node (ref "LED138") (pin "4-DIN") (pinfunction "DI_4-DIN") (pintype "input"))
    )
    (net (code "140") (name "Net-(LED138-DO)") (class "Default")
      (node (ref "LED138") (pin "2-DOUT") (pinfunction "DO_2-DOUT") (pintype "output"))
      (node (ref "LED139") (pin "4-DIN") (pinfunction "DI_4-DIN") (pintype "input"))
    )
    (net (code "141") (name "Net-(LED139-DO)") (class "Default")
      (node (ref "LED139") (pin "2-DOUT") (pinfunction "DO_2-DOUT") (pintype "output"))
      (node (ref "LED140") (pin "4-DIN") (pinfunction "DI_4-DIN") (pintype "input"))
    )
    (net (code "142") (name "Net-(LED140-DO)") (class "Default")
      (node (ref "LED140") (pin "2-DOUT") (pinfunction "DO_2-DOUT") (pintype "output"))
      (node (ref "LED141") (pin "4-DIN") (pinfunction "DI_4-DIN") (pintype "input"))
    )
    (net (code "143") (name "Net-(LED141-DO)") (class "Default")
      (node (ref "LED141") (pin "2-DOUT") (pinfunction "DO_2-DOUT") (pintype "output"))
      (node (ref "LED142") (pin "4-DIN") (pinfunction "DI_4-DIN") (pintype "input"))
    )
    (net (code "144") (name "Net-(LED142-DO)") (class "Default")
      (node (ref "LED142") (pin "2-DOUT") (pinfunction "DO_2-DOUT") (pintype "output"))
      (node (ref "LED143") (pin "4-DIN") (pinfunction "DI_4-DIN") (pintype "input"))
    )
    (net (code "145") (name "Net-(LED143-DO)") (class "Default")
      (node (ref "LED143") (pin "2-DOUT") (pinfunction "DO_2-DOUT") (pintype "output"))
      (node (ref "LED144") (pin "4-DIN") (pinfunction "DI_4-DIN") (pintype "input"))
    )
    (net (code "146") (name "Net-(LED144-DO)") (class "Default")
      (node (ref "LED144") (pin "2-DOUT") (pinfunction "DO_2-DOUT") (pintype "output"))
      (node (ref "LED145") (pin "4-DIN") (pinfunction "DI_4-DIN") (pintype "input"))
    )
    (net (code "147") (name "Net-(LED145-DO)") (class "Default")
      (node (ref "LED145") (pin "2-DOUT") (pinfunction "DO_2-DOUT") (pintype "output"))
      (node (ref "LED146") (pin "4-DIN") (pinfunction "DI_4-DIN") (pintype "input"))
    )
    (net (code "148") (name "Net-(LED146-DO)") (class "Default")
      (node (ref "LED146") (pin "2-DOUT") (pinfunction "DO_2-DOUT") (pintype "output"))
      (node (ref "LED147") (pin "4-DIN") (pinfunction "DI_4-DIN") (pintype "input"))
    )
    (net (code "149") (name "Net-(LED147-DO)") (class "Default")
      (node (ref "LED147") (pin "2-DOUT") (pinfunction "DO_2-DOUT") (pintype "output"))
      (node (ref "LED148") (pin "4-DIN") (pinfunction "DI_4-DIN") (pintype "input"))
    )
    (net (code "150") (name "Net-(LED148-DO)") (class "Default")
      (node (ref "LED148") (pin "2-DOUT") (pinfunction "DO_2-DOUT") (pintype "output"))
      (node (ref "LED149") (pin "4-DIN") (pinfunction "DI_4-DIN") (pintype "input"))
    )
    (net (code "151") (name "Net-(LED149-DO)") (class "Default")
      (node (ref "LED149") (pin "2-DOUT") (pinfunction "DO_2-DOUT") (pintype "output"))
      (node (ref "LED150") (pin "4-DIN") (pinfunction "DI_4-DIN") (pintype "input"))
    )
    (net (code "152") (name "Net-(LED150-DO)") (class "Default")
      (node (ref "LED150") (pin "2-DOUT") (pinfunction "DO_2-DOUT") (pintype "output"))
      (node (ref "LED151") (pin "4-DIN") (pinfunction "DI_4-DIN") (pintype "input"))
    )
    (net (code "153") (name "Net-(LED151-DO)") (class "Default")
      (node (ref "LED151") (pin "2-DOUT") (pinfunction "DO_2-DOUT") (pintype "output"))
      (node (ref "LED152") (pin "4-DIN") (pinfunction "DI_4-DIN") (pintype "input"))
    )
    (net (code "154") (name "Net-(LED152-DO)") (class "Default")
      (node (ref "LED152") (pin "2-DOUT") (pinfunction "DO_2-DOUT") (pintype "output"))
      (node (ref "LED153") (pin "4-DIN") (pinfunction "DI_4-DIN") (pintype "input"))
    )
    (net (code "155") (name "Net-(LED153-DO)") (class "Default")
      (node (ref "LED153") (pin "2-DOUT") (pinfunction "DO_2-DOUT") (pintype "output"))
      (node (ref "LED154") (pin "4-DIN") (pinfunction "DI_4-DIN") (pintype "input"))
    )
    (net (code "156") (name "Net-(LED154-DO)") (class "Default")
      (node (ref "JP7") (pin "1") (pinfunction "1_1") (pintype "passive"))
      (node (ref "LED154") (pin "2-DOUT") (pinfunction "DO_2-DOUT") (pintype "output"))
    )
    (net (code "157") (name "VCC") (class "Default")
      (node (ref "JP1") (pin "1") (pinfunction "1_1") (pintype "passive"))
      (node (ref "JP2") (pin "1") (pinfunction "1_1") (pintype "passive"))
      (node (ref "JP3") (pin "1") (pinfunction "1_1") (pintype "passive"))
      (node (ref "JP4") (pin "1") (pinfunction "1_1") (pintype "passive"))
      (node (ref "JP5") (pin "1") (pinfunction "1_1") (pintype "passive"))
      (node (ref "LED1") (pin "1-VDD") (pinfunction "VDD_1-VDD") (pintype "power_in"))
      (node (ref "LED10") (pin "1-VDD") (pinfunction "VDD_1-VDD") (pintype "power_in"))
      (node (ref "LED100") (pin "1-VDD") (pinfunction "VDD_1-VDD") (pintype "power_in"))
      (node (ref "LED101") (pin "1-VDD") (pinfunction "VDD_1-VDD") (pintype "power_in"))
      (node (ref "LED102") (pin "1-VDD") (pinfunction "VDD_1-VDD") (pintype "power_in"))
      (node (ref "LED103") (pin "1-VDD") (pinfunction "VDD_1-VDD") (pintype "power_in"))
      (node (ref "LED104") (pin "1-VDD") (pinfunction "VDD_1-VDD") (pintype "power_in"))
      (node (ref "LED105") (pin "1-VDD") (pinfunction "VDD_1-VDD") (pintype "power_in"))
      (node (ref "LED106") (pin "1-VDD") (pinfunction "VDD_1-VDD") (pintype "power_in"))
      (node (ref "LED107") (pin "1-VDD") (pinfunction "VDD_1-VDD") (pintype "power_in"))
      (node (ref "LED108") (pin "1-VDD") (pinfunction "VDD_1-VDD") (pintype "power_in"))
      (node (ref "LED109") (pin "1-VDD") (pinfunction "VDD_1-VDD") (pintype "power_in"))
      (node (ref "LED11") (pin "1-VDD") (pinfunction "VDD_1-VDD") (pintype "power_in"))
      (node (ref "LED110") (pin "1-VDD") (pinfunction "VDD_1-VDD") (pintype "power_in"))
      (node (ref "LED111") (pin "1-VDD") (pinfunction "VDD_1-VDD") (pintype "power_in"))
      (node (ref "LED112") (pin "1-VDD") (pinfunction "VDD_1-VDD") (pintype "power_in"))
      (node (ref "LED113") (pin "1-VDD") (pinfunction "VDD_1-VDD") (pintype "power_in"))
      (node (ref "LED114") (pin "1-VDD") (pinfunction "VDD_1-VDD") (pintype "power_in"))
      (node (ref "LED115") (pin "1-VDD") (pinfunction "VDD_1-VDD") (pintype "power_in"))
      (node (ref "LED116") (pin "1-VDD") (pinfunction "VDD_1-VDD") (pintype "power_in"))
      (node (ref "LED117") (pin "1-VDD") (pinfunction "VDD_1-VDD") (pintype "power_in"))
      (node (ref "LED118") (pin "1-VDD") (pinfunction "VDD_1-VDD") (pintype "power_in"))
      (node (ref "LED119") (pin "1-VDD") (pinfunction "VDD_1-VDD") (pintype "power_in"))
      (node (ref "LED12") (pin "1-VDD") (pinfunction "VDD_1-VDD") (pintype "power_in"))
      (node (ref "LED120") (pin "1-VDD") (pinfunction "VDD_1-VDD") (pintype "power_in"))
      (node (ref "LED121") (pin "1-VDD") (pinfunction "VDD_1-VDD") (pintype "power_in"))
      (node (ref "LED122") (pin "1-VDD") (pinfunction "VDD_1-VDD") (pintype "power_in"))
      (node (ref "LED123") (pin "1-VDD") (pinfunction "VDD_1-VDD") (pintype "power_in"))
      (node (ref "LED124") (pin "1-VDD") (pinfunction "VDD_1-VDD") (pintype "power_in"))
      (node (ref "LED125") (pin "1-VDD") (pinfunction "VDD_1-VDD") (pintype "power_in"))
      (node (ref "LED126") (pin "1-VDD") (pinfunction "VDD_1-VDD") (pintype "power_in"))
      (node (ref "LED127") (pin "1-VDD") (pinfunction "VDD_1-VDD") (pintype "power_in"))
      (node (ref "LED128") (pin "1-VDD") (pinfunction "VDD_1-VDD") (pintype "power_in"))
      (node (ref "LED129") (pin "1-VDD") (pinfunction "VDD_1-VDD") (pintype "power_in"))
      (node (ref "LED13") (pin "1-VDD") (pinfunction "VDD_1-VDD") (pintype "power_in"))
      (node (ref "LED130") (pin "1-VDD") (pinfunction "VDD_1-VDD") (pintype "power_in"))
      (node (ref "LED131") (pin "1-VDD") (pinfunction "VDD_1-VDD") (pintype "power_in"))
      (node (ref "LED132") (pin "1-VDD") (pinfunction "VDD_1-VDD") (pintype "power_in"))
      (node (ref "LED133") (pin "1-VDD") (pinfunction "VDD_1-VDD") (pintype "power_in"))
      (node (ref "LED134") (pin "1-VDD") (pinfunction "VDD_1-VDD") (pintype "power_in"))
      (node (ref "LED135") (pin "1-VDD") (pinfunction "VDD_1-VDD") (pintype "power_in"))
      (node (ref "LED136") (pin "1-VDD") (pinfunction "VDD_1-VDD") (pintype "power_in"))
      (node (ref "LED137") (pin "1-VDD") (pinfunction "VDD_1-VDD") (pintype "power_in"))
      (node (ref "LED138") (pin "1-VDD") (pinfunction "VDD_1-VDD") (pintype "power_in"))
      (node (ref "LED139") (pin "1-VDD") (pinfunction "VDD_1-VDD") (pintype "power_in"))
      (node (ref "LED14") (pin "1-VDD") (pinfunction "VDD_1-VDD") (pintype "power_in"))
      (node (ref "LED140") (pin "1-VDD") (pinfunction "VDD_1-VDD") (pintype "power_in"))
      (node (ref "LED141") (pin "1-VDD") (pinfunction "VDD_1-VDD") (pintype "power_in"))
      (node (ref "LED142") (pin "1-VDD") (pinfunction "VDD_1-VDD") (pintype "power_in"))
      (node (ref "LED143") (pin "1-VDD") (pinfunction "VDD_1-VDD") (pintype "power_in"))
      (node (ref "LED144") (pin "1-VDD") (pinfunction "VDD_1-VDD") (pintype "power_in"))
      (node (ref "LED145") (pin "1-VDD") (pinfunction "VDD_1-VDD") (pintype "power_in"))
      (node (ref "LED146") (pin "1-VDD") (pinfunction "VDD_1-VDD") (pintype "power_in"))
      (node (ref "LED147") (pin "1-VDD") (pinfunction "VDD_1-VDD") (pintype "power_in"))
      (node (ref "LED148") (pin "1-VDD") (pinfunction "VDD_1-VDD") (pintype "power_in"))
      (node (ref "LED149") (pin "1-VDD") (pinfunction "VDD_1-VDD") (pintype "power_in"))
      (node (ref "LED15") (pin "1-VDD") (pinfunction "VDD_1-VDD") (pintype "power_in"))
      (node (ref "LED150") (pin "1-VDD") (pinfunction "VDD_1-VDD") (pintype "power_in"))
      (node (ref "LED151") (pin "1-VDD") (pinfunction "VDD_1-VDD") (pintype "power_in"))
      (node (ref "LED152") (pin "1-VDD") (pinfunction "VDD_1-VDD") (pintype "power_in"))
      (node (ref "LED153") (pin "1-VDD") (pinfunction "VDD_1-VDD") (pintype "power_in"))
      (node (ref "LED154") (pin "1-VDD") (pinfunction "VDD_1-VDD") (pintype "power_in"))
      (node (ref "LED16") (pin "1-VDD") (pinfunction "VDD_1-VDD") (pintype "power_in"))
      (node (ref "LED17") (pin "1-VDD") (pinfunction "VDD_1-VDD") (pintype "power_in"))
      (node (ref "LED18") (pin "1-VDD") (pinfunction "VDD_1-VDD") (pintype "power_in"))
      (node (ref "LED19") (pin "1-VDD") (pinfunction "VDD_1-VDD") (pintype "power_in"))
      (node (ref "LED2") (pin "1-VDD") (pinfunction "VDD_1-VDD") (pintype "power_in"))
      (node (ref "LED20") (pin "1-VDD") (pinfunction "VDD_1-VDD") (pintype "power_in"))
      (node (ref "LED21") (pin "1-VDD") (pinfunction "VDD_1-VDD") (pintype "power_in"))
      (node (ref "LED22") (pin "1-VDD") (pinfunction "VDD_1-VDD") (pintype "power_in"))
      (node (ref "LED23") (pin "1-VDD") (pinfunction "VDD_1-VDD") (pintype "power_in"))
      (node (ref "LED24") (pin "1-VDD") (pinfunction "VDD_1-VDD") (pintype "power_in"))
      (node (ref "LED25") (pin "1-VDD") (pinfunction "VDD_1-VDD") (pintype "power_in"))
      (node (ref "LED26") (pin "1-VDD") (pinfunction "VDD_1-VDD") (pintype "power_in"))
      (node (ref "LED27") (pin "1-VDD") (pinfunction "VDD_1-VDD") (pintype "power_in"))
      (node (ref "LED28") (pin "1-VDD") (pinfunction "VDD_1-VDD") (pintype "power_in"))
      (node (ref "LED29") (pin "1-VDD") (pinfunction "VDD_1-VDD") (pintype "power_in"))
      (node (ref "LED3") (pin "1-VDD") (pinfunction "VDD_1-VDD") (pintype "power_in"))
      (node (ref "LED30") (pin "1-VDD") (pinfunction "VDD_1-VDD") (pintype "power_in"))
      (node (ref "LED31") (pin "1-VDD") (pinfunction "VDD_1-VDD") (pintype "power_in"))
      (node (ref "LED32") (pin "1-VDD") (pinfunction "VDD_1-VDD") (pintype "power_in"))
      (node (ref "LED33") (pin "1-VDD") (pinfunction "VDD_1-VDD") (pintype "power_in"))
      (node (ref "LED34") (pin "1-VDD") (pinfunction "VDD_1-VDD") (pintype "power_in"))
      (node (ref "LED35") (pin "1-VDD") (pinfunction "VDD_1-VDD") (pintype "power_in"))
      (node (ref "LED36") (pin "1-VDD") (pinfunction "VDD_1-VDD") (pintype "power_in"))
      (node (ref "LED37") (pin "1-VDD") (pinfunction "VDD_1-VDD") (pintype "power_in"))
      (node (ref "LED38") (pin "1-VDD") (pinfunction "VDD_1-VDD") (pintype "power_in"))
      (node (ref "LED39") (pin "1-VDD") (pinfunction "VDD_1-VDD") (pintype "power_in"))
      (node (ref "LED4") (pin "1-VDD") (pinfunction "VDD_1-VDD") (pintype "power_in"))
      (node (ref "LED40") (pin "1-VDD") (pinfunction "VDD_1-VDD") (pintype "power_in"))
      (node (ref "LED41") (pin "1-VDD") (pinfunction "VDD_1-VDD") (pintype "power_in"))
      (node (ref "LED42") (pin "1-VDD") (pinfunction "VDD_1-VDD") (pintype "power_in"))
      (node (ref "LED43") (pin "1-VDD") (pinfunction "VDD_1-VDD") (pintype "power_in"))
      (node (ref "LED44") (pin "1-VDD") (pinfunction "VDD_1-VDD") (pintype "power_in"))
      (node (ref "LED45") (pin "1-VDD") (pinfunction "VDD_1-VDD") (pintype "power_in"))
      (node (ref "LED46") (pin "1-VDD") (pinfunction "VDD_1-VDD") (pintype "power_in"))
      (node (ref "LED47") (pin "1-VDD") (pinfunction "VDD_1-VDD") (pintype "power_in"))
      (node (ref "LED48") (pin "1-VDD") (pinfunction "VDD_1-VDD") (pintype "power_in"))
      (node (ref "LED49") (pin "1-VDD") (pinfunction "VDD_1-VDD") (pintype "power_in"))
      (node (ref "LED5") (pin "1-VDD") (pinfunction "VDD_1-VDD") (pintype "power_in"))
      (node (ref "LED50") (pin "1-VDD") (pinfunction "VDD_1-VDD") (pintype "power_in"))
      (node (ref "LED51") (pin "1-VDD") (pinfunction "VDD_1-VDD") (pintype "power_in"))
      (node (ref "LED52") (pin "1-VDD") (pinfunction "VDD_1-VDD") (pintype "power_in"))
      (node (ref "LED53") (pin "1-VDD") (pinfunction "VDD_1-VDD") (pintype "power_in"))
      (node (ref "LED54") (pin "1-VDD") (pinfunction "VDD_1-VDD") (pintype "power_in"))
      (node (ref "LED55") (pin "1-VDD") (pinfunction "VDD_1-VDD") (pintype "power_in"))
      (node (ref "LED56") (pin "1-VDD") (pinfunction "VDD_1-VDD") (pintype "power_in"))
      (node (ref "LED57") (pin "1-VDD") (pinfunction "VDD_1-VDD") (pintype "power_in"))
      (node (ref "LED58") (pin "1-VDD") (pinfunction "VDD_1-VDD") (pintype "power_in"))
      (node (ref "LED59") (pin "1-VDD") (pinfunction "VDD_1-VDD") (pintype "power_in"))
      (node (ref "LED6") (pin "1-VDD") (pinfunction "VDD_1-VDD") (pintype "power_in"))
      (node (ref "LED60") (pin "1-VDD") (pinfunction "VDD_1-VDD") (pintype "power_in"))
      (node (ref "LED61") (pin "1-VDD") (pinfunction "VDD_1-VDD") (pintype "power_in"))
      (node (ref "LED62") (pin "1-VDD") (pinfunction "VDD_1-VDD") (pintype "power_in"))
      (node (ref "LED63") (pin "1-VDD") (pinfunction "VDD_1-VDD") (pintype "power_in"))
      (node (ref "LED64") (pin "1-VDD") (pinfunction "VDD_1-VDD") (pintype "power_in"))
      (node (ref "LED65") (pin "1-VDD") (pinfunction "VDD_1-VDD") (pintype "power_in"))
      (node (ref "LED66") (pin "1-VDD") (pinfunction "VDD_1-VDD") (pintype "power_in"))
      (node (ref "LED67") (pin "1-VDD") (pinfunction "VDD_1-VDD") (pintype "power_in"))
      (node (ref "LED68") (pin "1-VDD") (pinfunction "VDD_1-VDD") (pintype "power_in"))
      (node (ref "LED69") (pin "1-VDD") (pinfunction "VDD_1-VDD") (pintype "power_in"))
      (node (ref "LED7") (pin "1-VDD") (pinfunction "VDD_1-VDD") (pintype "power_in"))
      (node (ref "LED70") (pin "1-VDD") (pinfunction "VDD_1-VDD") (pintype "power_in"))
      (node (ref "LED71") (pin "1-VDD") (pinfunction "VDD_1-VDD") (pintype "power_in"))
      (node (ref "LED72") (pin "1-VDD") (pinfunction "VDD_1-VDD") (pintype "power_in"))
      (node (ref "LED73") (pin "1-VDD") (pinfunction "VDD_1-VDD") (pintype "power_in"))
      (node (ref "LED74") (pin "1-VDD") (pinfunction "VDD_1-VDD") (pintype "power_in"))
      (node (ref "LED75") (pin "1-VDD") (pinfunction "VDD_1-VDD") (pintype "power_in"))
      (node (ref "LED76") (pin "1-VDD") (pinfunction "VDD_1-VDD") (pintype "power_in"))
      (node (ref "LED77") (pin "1-VDD") (pinfunction "VDD_1-VDD") (pintype "power_in"))
      (node (ref "LED78") (pin "1-VDD") (pinfunction "VDD_1-VDD") (pintype "power_in"))
      (node (ref "LED79") (pin "1-VDD") (pinfunction "VDD_1-VDD") (pintype "power_in"))
      (node (ref "LED8") (pin "1-VDD") (pinfunction "VDD_1-VDD") (pintype "power_in"))
      (node (ref "LED80") (pin "1-VDD") (pinfunction "VDD_1-VDD") (pintype "power_in"))
      (node (ref "LED81") (pin "1-VDD") (pinfunction "VDD_1-VDD") (pintype "power_in"))
      (node (ref "LED82") (pin "1-VDD") (pinfunction "VDD_1-VDD") (pintype "power_in"))
      (node (ref "LED83") (pin "1-VDD") (pinfunction "VDD_1-VDD") (pintype "power_in"))
      (node (ref "LED84") (pin "1-VDD") (pinfunction "VDD_1-VDD") (pintype "power_in"))
      (node (ref "LED85") (pin "1-VDD") (pinfunction "VDD_1-VDD") (pintype "power_in"))
      (node (ref "LED86") (pin "1-VDD") (pinfunction "VDD_1-VDD") (pintype "power_in"))
      (node (ref "LED87") (pin "1-VDD") (pinfunction "VDD_1-VDD") (pintype "power_in"))
      (node (ref "LED88") (pin "1-VDD") (pinfunction "VDD_1-VDD") (pintype "power_in"))
      (node (ref "LED89") (pin "1-VDD") (pinfunction "VDD_1-VDD") (pintype "power_in"))
      (node (ref "LED9") (pin "1-VDD") (pinfunction "VDD_1-VDD") (pintype "power_in"))
      (node (ref "LED90") (pin "1-VDD") (pinfunction "VDD_1-VDD") (pintype "power_in"))
      (node (ref "LED91") (pin "1-VDD") (pinfunction "VDD_1-VDD") (pintype "power_in"))
      (node (ref "LED92") (pin "1-VDD") (pinfunction "VDD_1-VDD") (pintype "power_in"))
      (node (ref "LED93") (pin "1-VDD") (pinfunction "VDD_1-VDD") (pintype "power_in"))
      (node (ref "LED94") (pin "1-VDD") (pinfunction "VDD_1-VDD") (pintype "power_in"))
      (node (ref "LED95") (pin "1-VDD") (pinfunction "VDD_1-VDD") (pintype "power_in"))
      (node (ref "LED96") (pin "1-VDD") (pinfunction "VDD_1-VDD") (pintype "power_in"))
      (node (ref "LED97") (pin "1-VDD") (pinfunction "VDD_1-VDD") (pintype "power_in"))
      (node (ref "LED98") (pin "1-VDD") (pinfunction "VDD_1-VDD") (pintype "power_in"))
      (node (ref "LED99") (pin "1-VDD") (pinfunction "VDD_1-VDD") (pintype "power_in"))
    )
  )
)
